# sha2017_rev0_1_0_dev.net
KiCad netlist of a schematic drawn in EAGLE
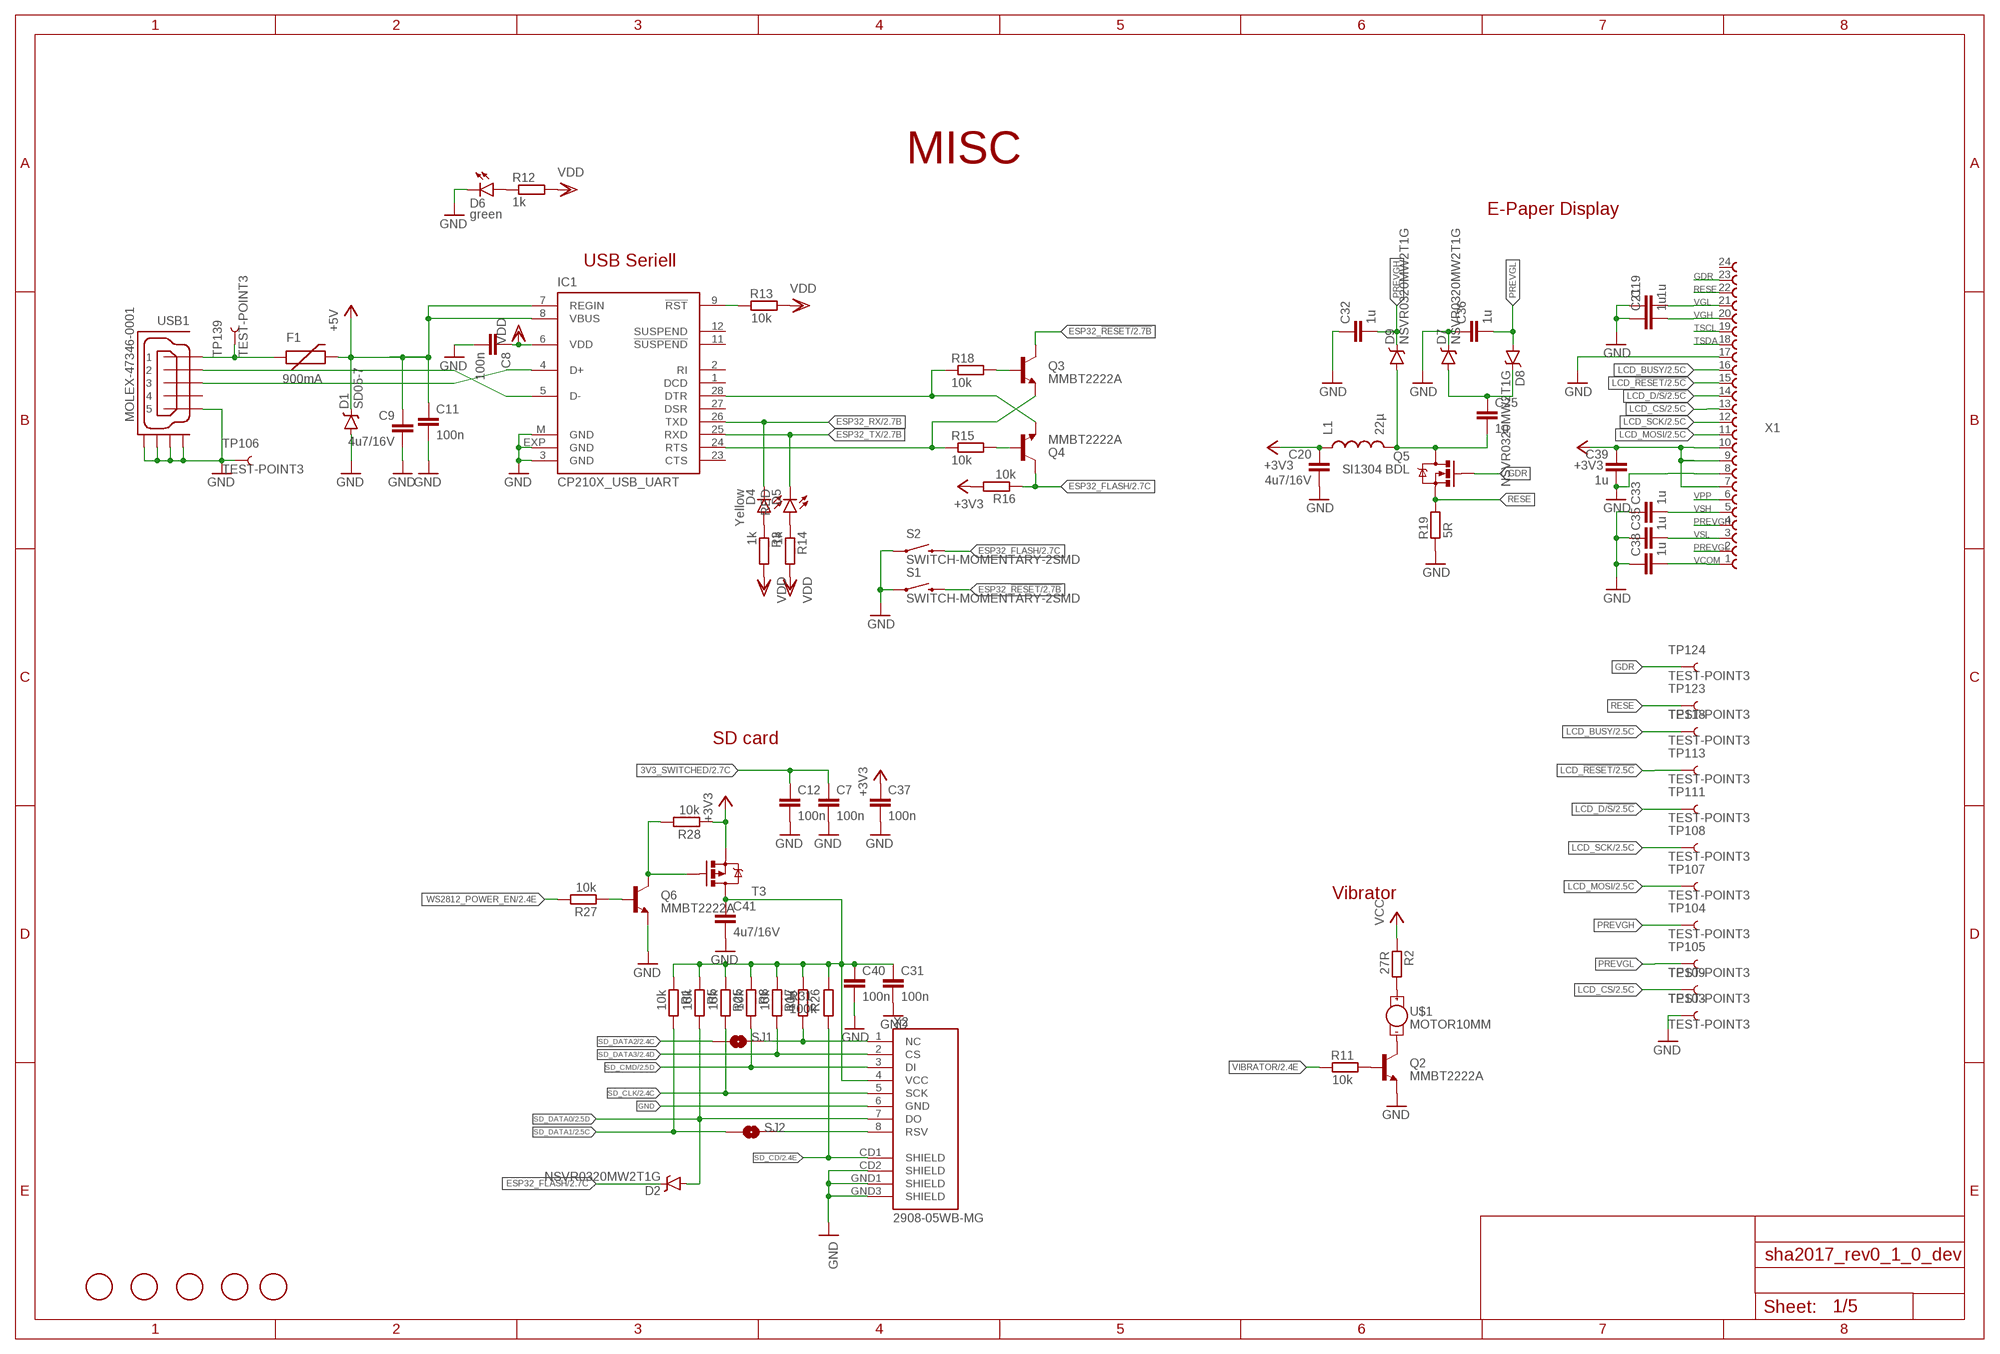
[diagram p0: schematic, sheet 1]
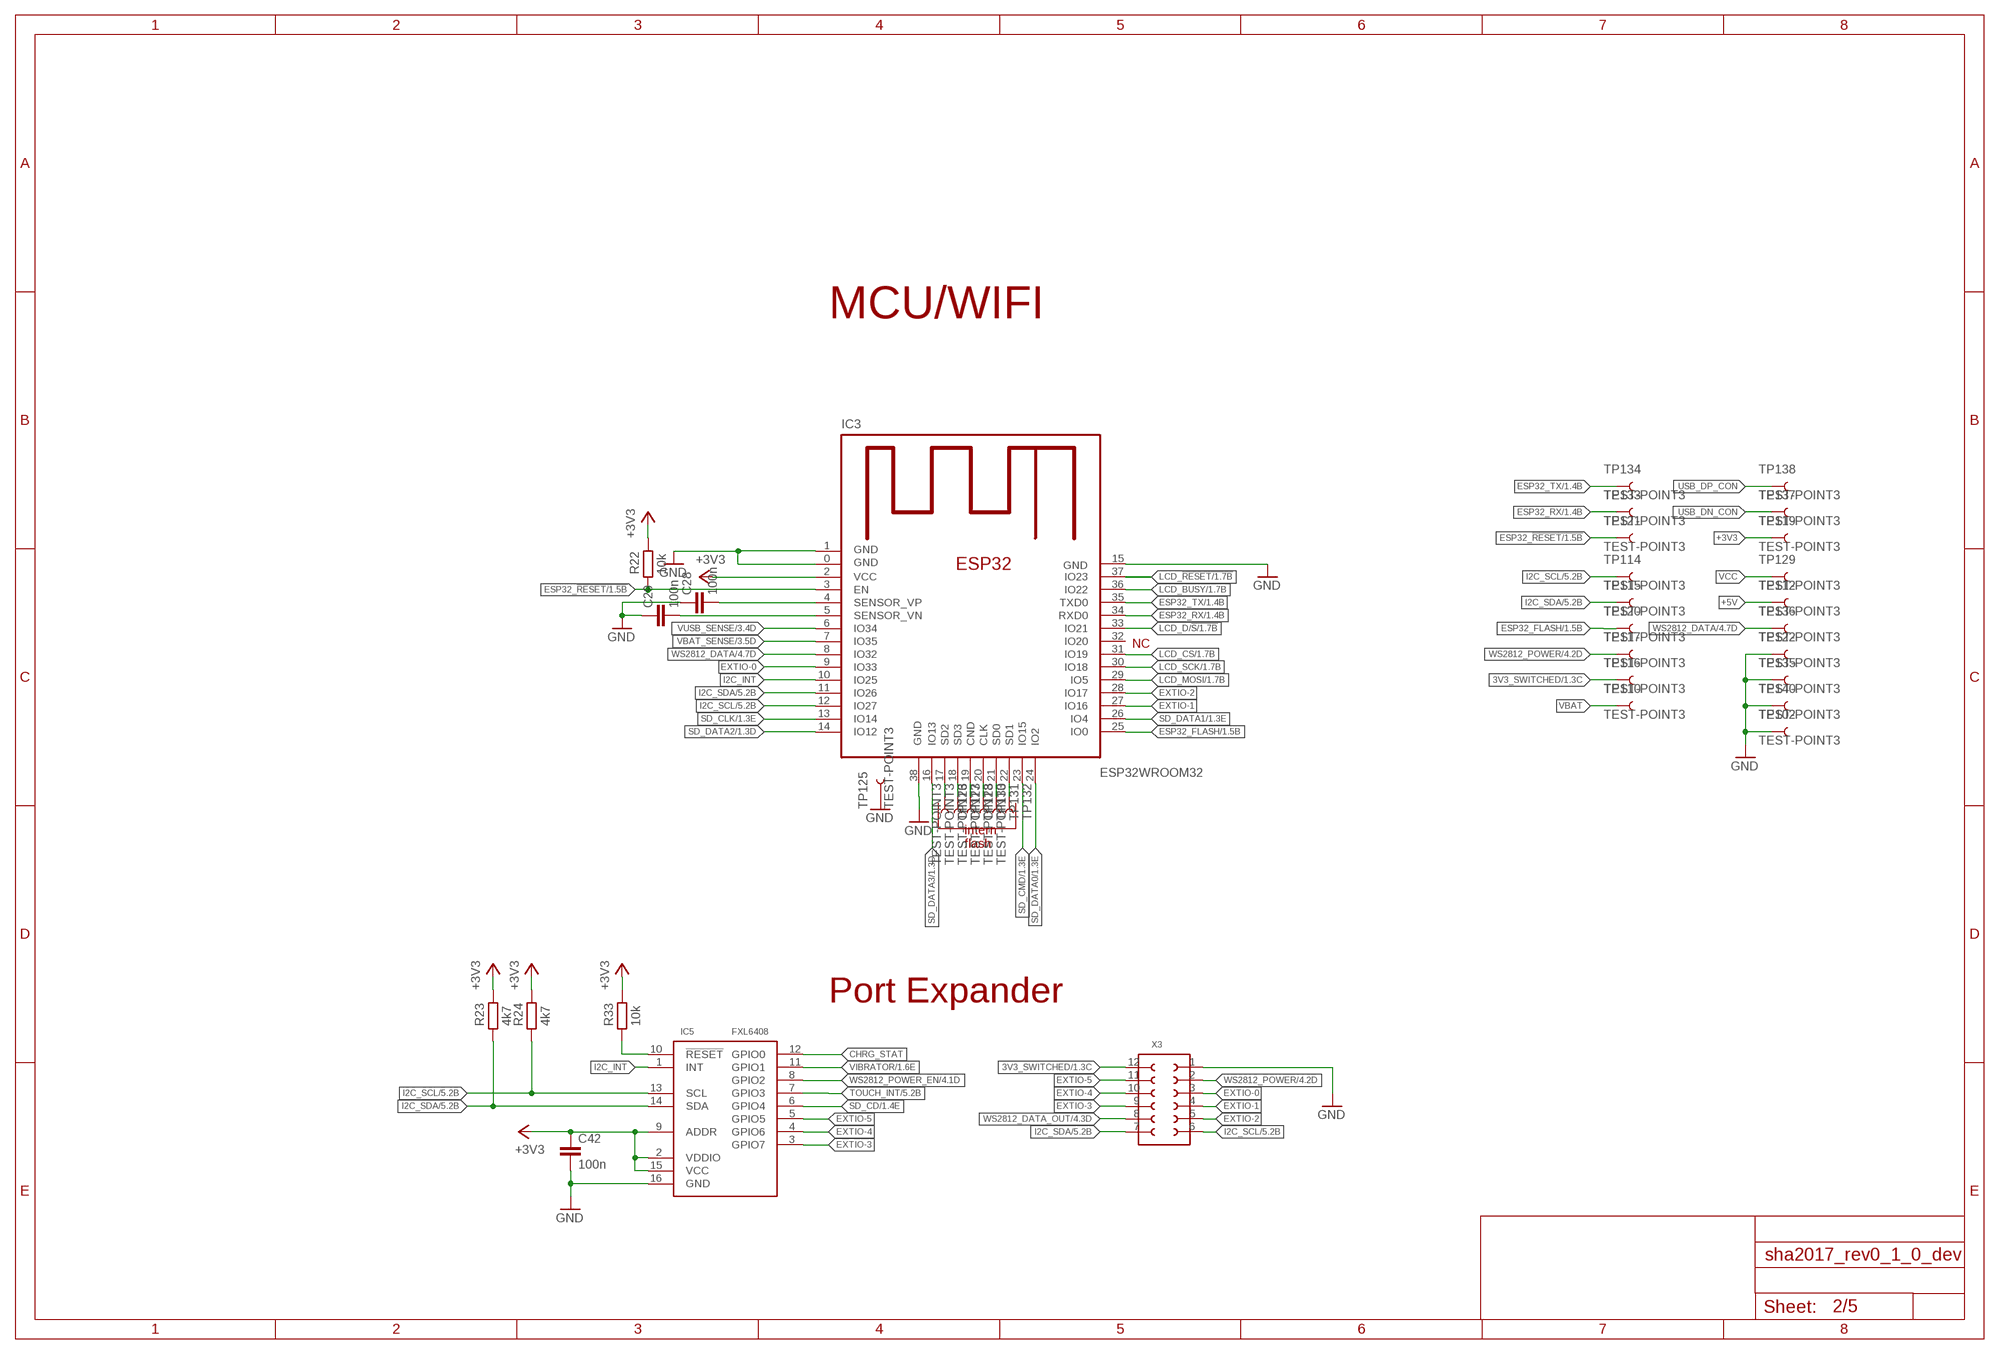
[diagram p1: schematic, sheet 2]
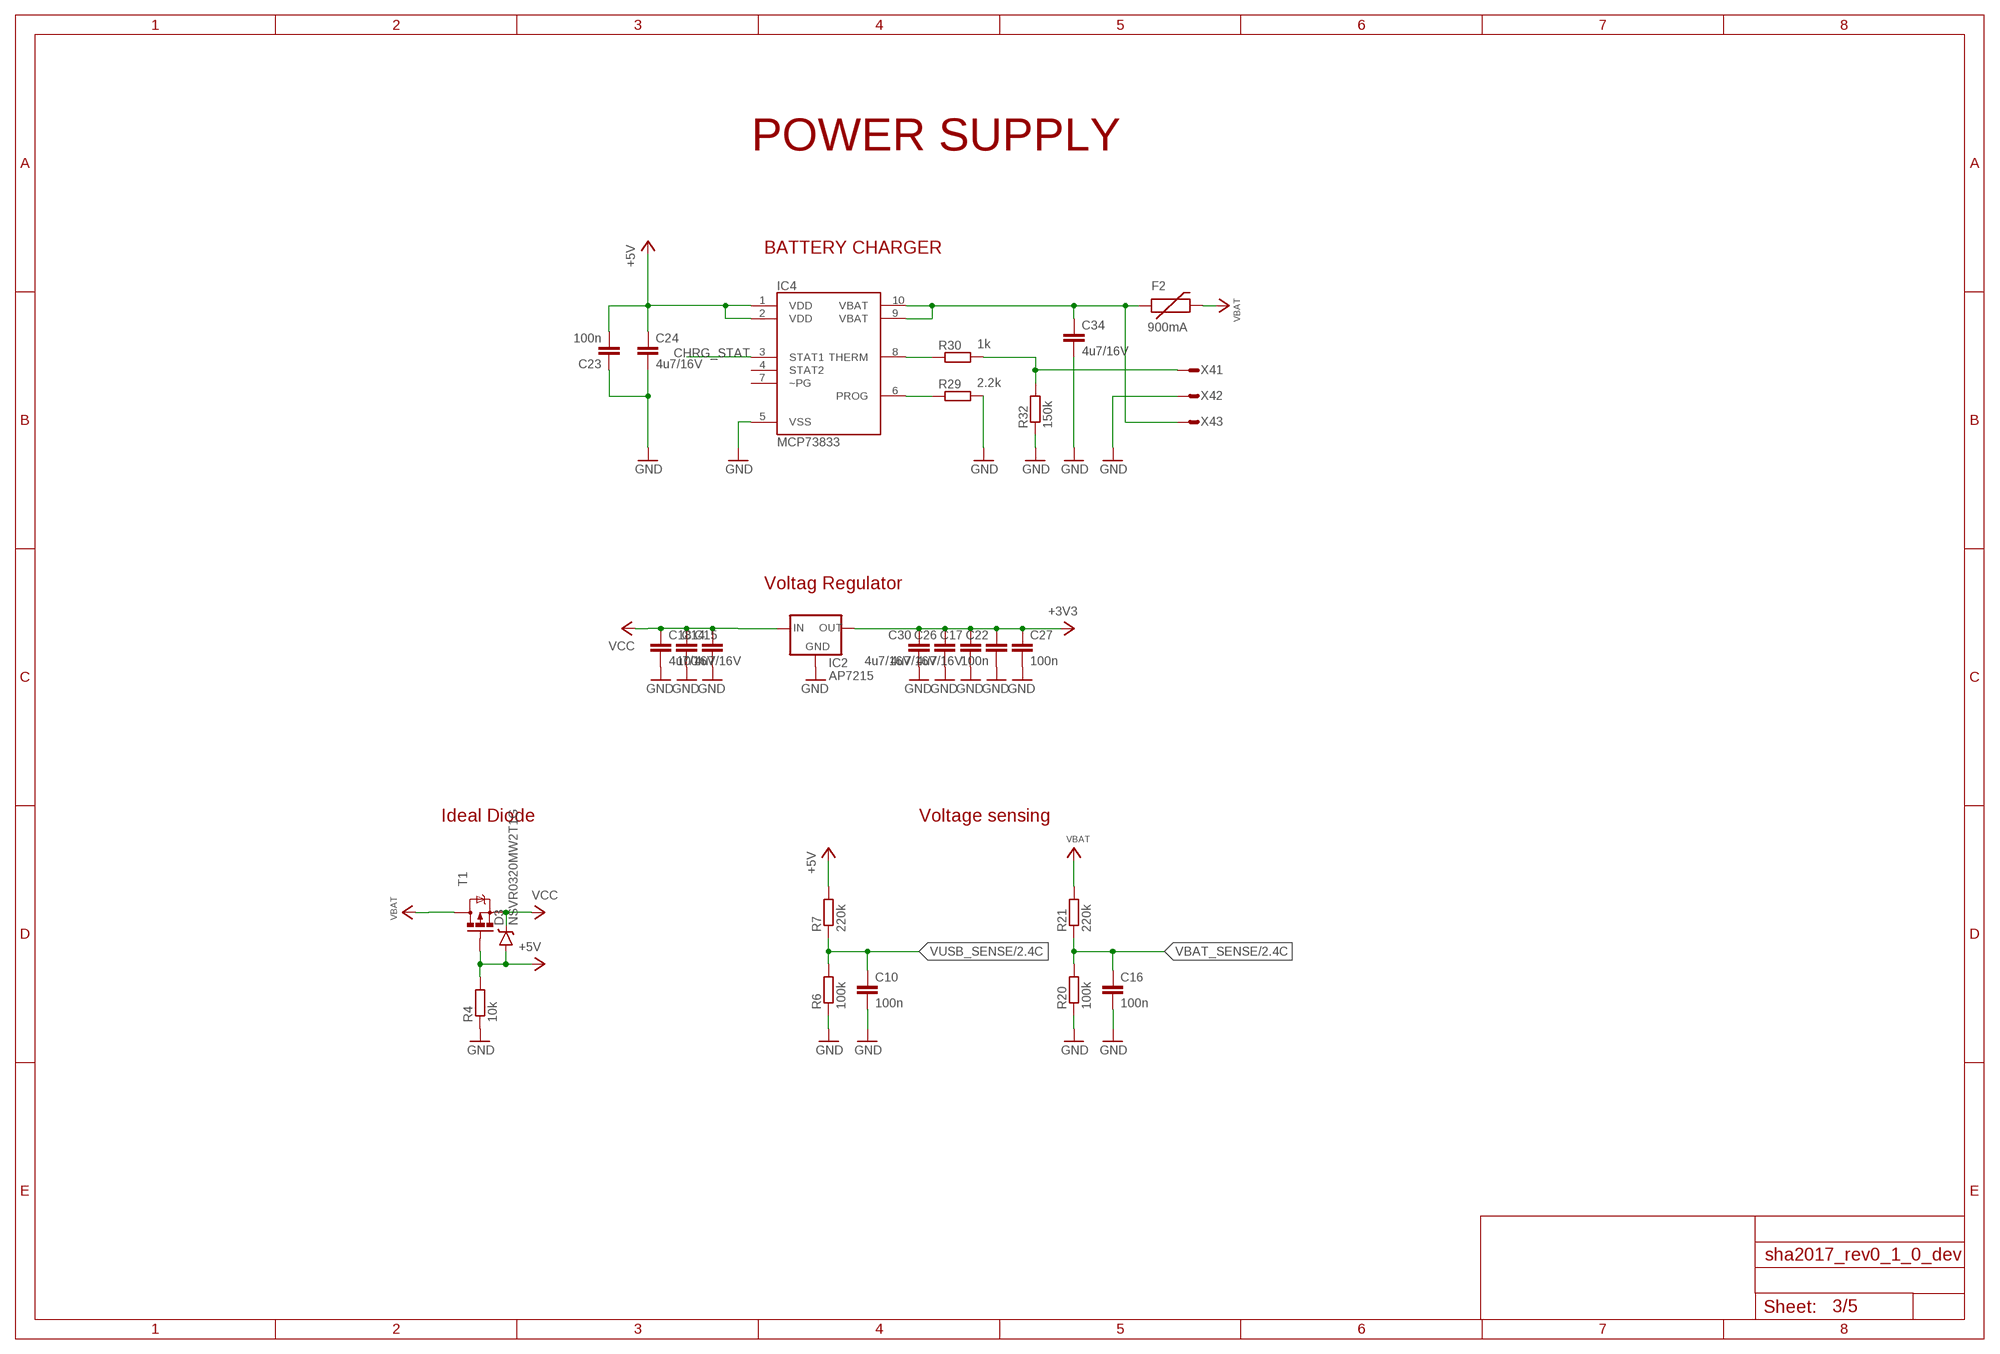
[diagram p2: schematic, sheet 3]
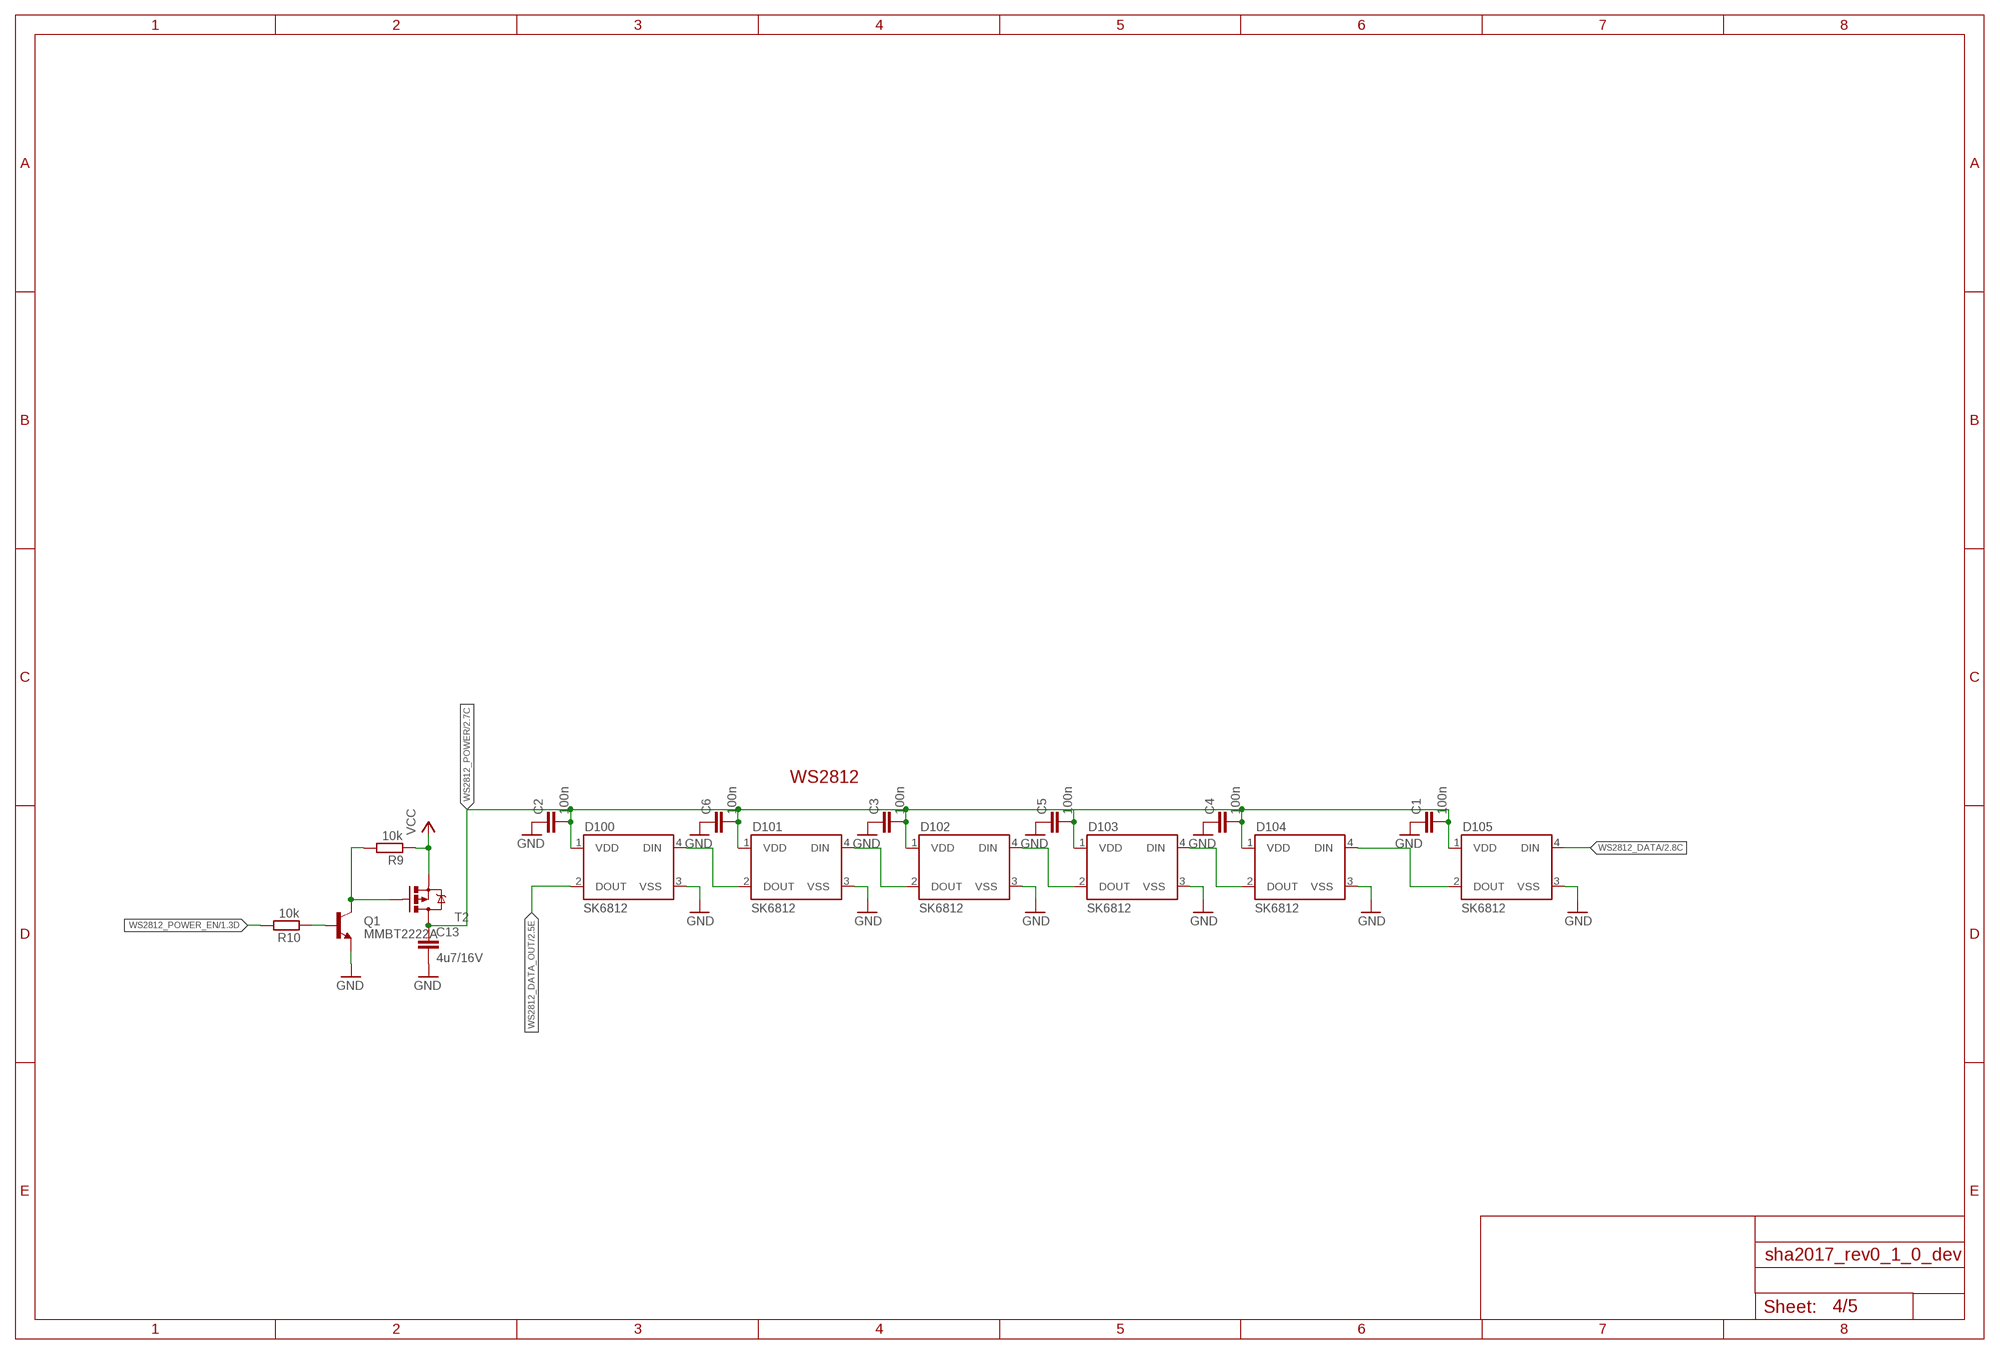
[diagram p3: schematic, sheet 4]
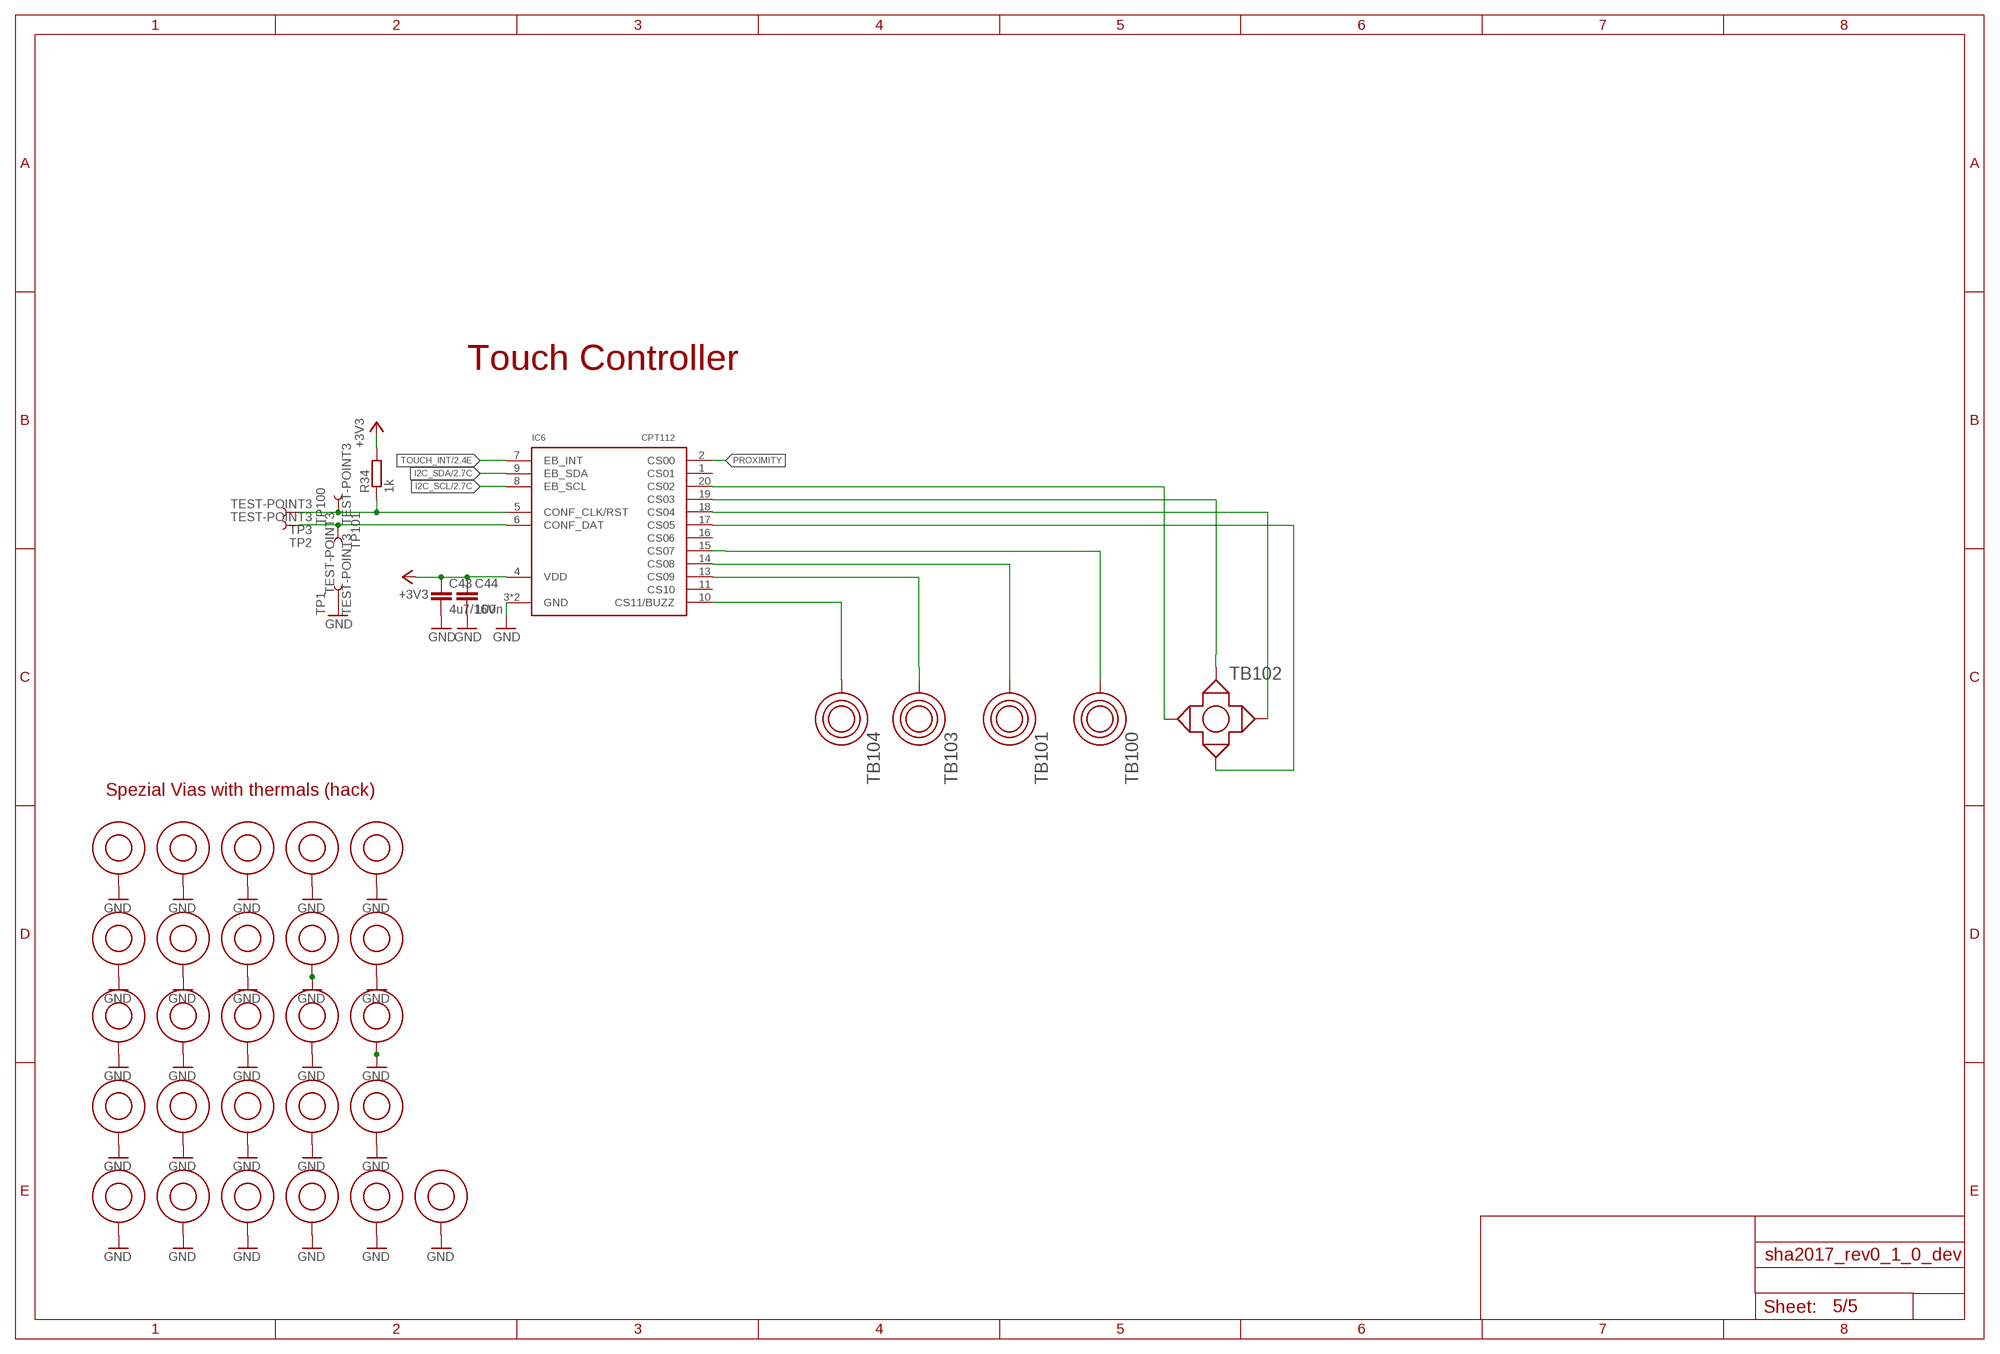
[diagram p4: schematic, sheet 5]

(export (version "E")
  (design (tool "Eeschema 10.0.6"))
  (components
    (comp (ref "C7")
      (value "100n")
      (footprint "eagle-import:C0603-DASHES")
      (fields (field (name "PARTNO") "GRM188R71H104KA93D"))
      (libsource (lib "eagle-import") (part "C0603-DASHES"))
    )
    (comp (ref "C8")
      (value "100n")
      (footprint "eagle-import:C0603-DASHES")
      (fields (field (name "PARTNO") "GRM188R71H104KA93D"))
      (libsource (lib "eagle-import") (part "C0603-DASHES"))
    )
    (comp (ref "C9")
      (value "4u7/16V")
      (footprint "eagle-import:C0805")
      (fields (field (name "PARTNO") "GRM21BR61C475KA88K"))
      (libsource (lib "eagle-import") (part "C-EUC0805"))
    )
    (comp (ref "C11")
      (value "100n")
      (footprint "eagle-import:C0603-DASHES")
      (fields (field (name "PARTNO") "GRM188R71H104KA93D"))
      (libsource (lib "eagle-import") (part "C0603-DASHES"))
    )
    (comp (ref "C12")
      (value "100n")
      (footprint "eagle-import:C0603-DASHES")
      (fields (field (name "PARTNO") "GRM188R71H104KA93D"))
      (libsource (lib "eagle-import") (part "C0603-DASHES"))
    )
    (comp (ref "C19")
      (value "1u")
      (footprint "eagle-import:C0603-DASHES")
      (fields (field (name "PARTNO") "GRM188R61E105KA12D"))
      (libsource (lib "eagle-import") (part "C0603-DASHES"))
    )
    (comp (ref "C20")
      (value "4u7/16V")
      (footprint "eagle-import:C0805")
      (fields (field (name "PARTNO") "GRM21BR61C475KA88K"))
      (libsource (lib "eagle-import") (part "C-EUC0805"))
    )
    (comp (ref "C21")
      (value "1u")
      (footprint "eagle-import:C0603-DASHES")
      (fields (field (name "PARTNO") "GRM188R61E105KA12D"))
      (libsource (lib "eagle-import") (part "C0603-DASHES"))
    )
    (comp (ref "C25")
      (value "1u")
      (footprint "eagle-import:C0603-DASHES")
      (fields (field (name "PARTNO") "GRM188R61E105KA12D"))
      (libsource (lib "eagle-import") (part "C0603-DASHES"))
    )
    (comp (ref "C31")
      (value "100n")
      (footprint "eagle-import:C0603-DASHES")
      (fields (field (name "PARTNO") "GRM188R71H104KA93D"))
      (libsource (lib "eagle-import") (part "C0603-DASHES"))
    )
    (comp (ref "C32")
      (value "1u")
      (footprint "eagle-import:C0603-DASHES")
      (fields (field (name "PARTNO") "GRM188R61E105KA12D"))
      (libsource (lib "eagle-import") (part "C0603-DASHES"))
    )
    (comp (ref "C33")
      (value "1u")
      (footprint "eagle-import:C0603-DASHES")
      (fields (field (name "PARTNO") "GRM188R61E105KA12D"))
      (libsource (lib "eagle-import") (part "C0603-DASHES"))
    )
    (comp (ref "C35")
      (value "1u")
      (footprint "eagle-import:C0603-DASHES")
      (fields (field (name "PARTNO") "GRM188R61E105KA12D"))
      (libsource (lib "eagle-import") (part "C0603-DASHES"))
    )
    (comp (ref "C36")
      (value "1u")
      (footprint "eagle-import:C0603-DASHES")
      (fields (field (name "PARTNO") "GRM188R61E105KA12D"))
      (libsource (lib "eagle-import") (part "C0603-DASHES"))
    )
    (comp (ref "C37")
      (value "100n")
      (footprint "eagle-import:C0603-DASHES")
      (fields (field (name "PARTNO") "GRM188R71H104KA93D"))
      (libsource (lib "eagle-import") (part "C0603-DASHES"))
    )
    (comp (ref "C38")
      (value "1u")
      (footprint "eagle-import:C0603-DASHES")
      (fields (field (name "PARTNO") "GRM188R61E105KA12D"))
      (libsource (lib "eagle-import") (part "C0603-DASHES"))
    )
    (comp (ref "C39")
      (value "1u")
      (footprint "eagle-import:C0603-DASHES")
      (fields (field (name "PARTNO") "GRM188R61E105KA12D"))
      (libsource (lib "eagle-import") (part "C0603-DASHES"))
    )
    (comp (ref "C40")
      (value "100n")
      (footprint "eagle-import:C0603-DASHES")
      (fields (field (name "PARTNO") "GRM188R71H104KA93D"))
      (libsource (lib "eagle-import") (part "C0603-DASHES"))
    )
    (comp (ref "C41")
      (value "4u7/16V")
      (footprint "eagle-import:C0805")
      (fields (field (name "PARTNO") "GRM21BR61C475KA88K"))
      (libsource (lib "eagle-import") (part "C-EUC0805"))
    )
    (comp (ref "D1")
      (value "SD05-7")
      (footprint "eagle-import:SOD-323")
      (libsource (lib "eagle-import") (part "DIODE-SCHOTTKY-PMEG4005EJ"))
    )
    (comp (ref "D2")
      (value "NSVR0320MW2T1G")
      (footprint "eagle-import:SOD-323")
      (fields (field (name "PARTNO") "BAT20JFILM"))
      (libsource (lib "eagle-import") (part "BAT20JFILM"))
    )
    (comp (ref "D4")
      (value "Yellow")
      (footprint "eagle-import:LED-0603")
      (libsource (lib "eagle-import") (part "LED0603"))
    )
    (comp (ref "D5")
      (value "RED")
      (footprint "eagle-import:LED-0603")
      (libsource (lib "eagle-import") (part "LED0603"))
    )
    (comp (ref "D6")
      (value "green")
      (footprint "eagle-import:LED-0603")
      (libsource (lib "eagle-import") (part "LED0603"))
    )
    (comp (ref "D7")
      (value "NSVR0320MW2T1G")
      (footprint "eagle-import:SOD-323")
      (fields (field (name "PARTNO") "BAT20JFILM"))
      (libsource (lib "eagle-import") (part "BAT20JFILM"))
    )
    (comp (ref "D8")
      (value "NSVR0320MW2T1G")
      (footprint "eagle-import:SOD-323")
      (fields (field (name "PARTNO") "BAT20JFILM"))
      (libsource (lib "eagle-import") (part "BAT20JFILM"))
    )
    (comp (ref "D9")
      (value "NSVR0320MW2T1G")
      (footprint "eagle-import:SOD-323")
      (fields (field (name "PARTNO") "BAT20JFILM"))
      (libsource (lib "eagle-import") (part "BAT20JFILM"))
    )
    (comp (ref "F1")
      (value "900mA")
      (footprint "eagle-import:PTC-1206")
      (libsource (lib "eagle-import") (part "PTCSMD"))
    )
    (comp (ref "FD1")
      (value "FIDUCIAL")
      (footprint "eagle-import:FIDUCIAL_1MM")
      (fields (field (name "PARTNO") "NAP"))
      (libsource (lib "eagle-import") (part "FIDUCIAL"))
    )
    (comp (ref "FD2")
      (value "FIDUCIAL")
      (footprint "eagle-import:FIDUCIAL_1MM")
      (fields (field (name "PARTNO") "NAP"))
      (libsource (lib "eagle-import") (part "FIDUCIAL"))
    )
    (comp (ref "FD3")
      (value "FIDUCIAL")
      (footprint "eagle-import:FIDUCIAL_1MM")
      (fields (field (name "PARTNO") "NAP"))
      (libsource (lib "eagle-import") (part "FIDUCIAL"))
    )
    (comp (ref "FD4")
      (value "FIDUCIAL")
      (footprint "eagle-import:FIDUCIAL_1MM")
      (fields (field (name "PARTNO") "NAP"))
      (libsource (lib "eagle-import") (part "FIDUCIAL"))
    )
    (comp (ref "FD5")
      (value "FIDUCIAL")
      (footprint "eagle-import:FIDUCIAL_1MM")
      (fields (field (name "PARTNO") "NAP"))
      (libsource (lib "eagle-import") (part "FIDUCIAL"))
    )
    (comp (ref "IC1")
      (value "CP210X_USB_UART")
      (footprint "eagle-import:MLP28")
      (fields (field (name "PARTNO") "CP2102-GMR"))
      (libsource (lib "eagle-import") (part "CP210X_USB_UART"))
    )
    (comp (ref "L1")
      (value "22µ")
      (footprint "eagle-import:1210")
      (fields (field (name "PARTNO") "NLCV32T-220K-EF"))
      (libsource (lib "eagle-import") (part "INDUCTOR1210"))
    )
    (comp (ref "Q2")
      (value "MMBT2222A")
      (footprint "eagle-import:SOT23-3")
      (fields (field (name "PARTNO") "BC817-25,215"))
      (libsource (lib "eagle-import") (part "TRANSISTOR_NPNMMBT2222A"))
    )
    (comp (ref "Q3")
      (value "MMBT2222A")
      (footprint "eagle-import:SOT23-3")
      (fields (field (name "PARTNO") "BC817-25,215"))
      (libsource (lib "eagle-import") (part "TRANSISTOR_NPNMMBT2222A"))
    )
    (comp (ref "Q4")
      (value "MMBT2222A")
      (footprint "eagle-import:SOT23-3")
      (fields (field (name "PARTNO") "BC817-25,215"))
      (libsource (lib "eagle-import") (part "TRANSISTOR_NPNMMBT2222A"))
    )
    (comp (ref "Q5")
      (value "SI1304 BDL")
      (footprint "eagle-import:SOT323")
      (fields (field (name "PARTNO") "SI1308EDL-T1-GE3"))
      (libsource (lib "eagle-import") (part "MOSFET-NCHANNEL2N7002PW"))
    )
    (comp (ref "Q6")
      (value "MMBT2222A")
      (footprint "eagle-import:SOT23-3")
      (fields (field (name "PARTNO") "BC817-25,215"))
      (libsource (lib "eagle-import") (part "TRANSISTOR_NPNMMBT2222A"))
    )
    (comp (ref "R1")
      (value "10k")
      (footprint "eagle-import:R0603-DASHES")
      (fields (field (name "PARTNO") "ERJ-3GEYJ103V"))
      (libsource (lib "eagle-import") (part "R0603-DASHES"))
    )
    (comp (ref "R2")
      (value "27R")
      (footprint "eagle-import:R0603-DASHES")
      (fields (field (name "PARTNO") "ERJ-3GEYJ220V"))
      (libsource (lib "eagle-import") (part "R0603-DASHES"))
    )
    (comp (ref "R3")
      (value "1k")
      (footprint "eagle-import:R0603-DASHES")
      (fields (field (name "PARTNO") "ERJ-3GEYJ102V"))
      (libsource (lib "eagle-import") (part "sha2017_rev0_1_0_dev_R0603-DASHES"))
    )
    (comp (ref "R5")
      (value "10k")
      (footprint "eagle-import:R0603-DASHES")
      (fields (field (name "PARTNO") "ERJ-3GEYJ103V"))
      (libsource (lib "eagle-import") (part "R0603-DASHES"))
    )
    (comp (ref "R8")
      (value "10k")
      (footprint "eagle-import:R0603-DASHES")
      (fields (field (name "PARTNO") "ERJ-3GEYJ103V"))
      (libsource (lib "eagle-import") (part "R0603-DASHES"))
    )
    (comp (ref "R11")
      (value "10k")
      (footprint "eagle-import:R0603-DASHES")
      (fields (field (name "PARTNO") "ERJ-3GEYJ103V"))
      (libsource (lib "eagle-import") (part "R0603-DASHES"))
    )
    (comp (ref "R12")
      (value "1k")
      (footprint "eagle-import:R0603-DASHES")
      (fields (field (name "PARTNO") "ERJ-3GEYJ102V"))
      (libsource (lib "eagle-import") (part "sha2017_rev0_1_0_dev_R0603-DASHES"))
    )
    (comp (ref "R13")
      (value "10k")
      (footprint "eagle-import:R0603-DASHES")
      (fields (field (name "PARTNO") "ERJ-3GEYJ103V"))
      (libsource (lib "eagle-import") (part "sha2017_rev0_1_0_dev_R0603-DASHES"))
    )
    (comp (ref "R14")
      (value "1k")
      (footprint "eagle-import:R0603-DASHES")
      (fields (field (name "PARTNO") "ERJ-3GEYJ102V"))
      (libsource (lib "eagle-import") (part "sha2017_rev0_1_0_dev_R0603-DASHES"))
    )
    (comp (ref "R15")
      (value "10k")
      (footprint "eagle-import:R0603-DASHES")
      (fields (field (name "PARTNO") "ERJ-3GEYJ103V"))
      (libsource (lib "eagle-import") (part "sha2017_rev0_1_0_dev_R0603-DASHES"))
    )
    (comp (ref "R16")
      (value "10k")
      (footprint "eagle-import:R0603-DASHES")
      (fields (field (name "PARTNO") "ERJ-3GEYJ103V"))
      (libsource (lib "eagle-import") (part "sha2017_rev0_1_0_dev_R0603-DASHES"))
    )
    (comp (ref "R17")
      (value "10k")
      (footprint "eagle-import:R0603-DASHES")
      (fields (field (name "PARTNO") "ERJ-3GEYJ103V"))
      (libsource (lib "eagle-import") (part "sha2017_rev0_1_0_dev_R0603-DASHES"))
    )
    (comp (ref "R18")
      (value "10k")
      (footprint "eagle-import:R0603-DASHES")
      (fields (field (name "PARTNO") "ERJ-3GEYJ103V"))
      (libsource (lib "eagle-import") (part "sha2017_rev0_1_0_dev_R0603-DASHES"))
    )
    (comp (ref "R19")
      (value "5R")
      (footprint "eagle-import:R0603-DASHES")
      (fields (field (name "PARTNO") "ERJ-3GEYJ5R1V"))
      (libsource (lib "eagle-import") (part "sha2017_rev0_1_0_dev_R0603-DASHES"))
    )
    (comp (ref "R25")
      (value "10k")
      (footprint "eagle-import:R0603-DASHES")
      (fields (field (name "PARTNO") "ERJ-3GEYJ103V"))
      (libsource (lib "eagle-import") (part "sha2017_rev0_1_0_dev_R0603-DASHES"))
    )
    (comp (ref "R26")
      (value "10k")
      (footprint "eagle-import:R0603-DASHES")
      (fields (field (name "PARTNO") "ERJ-3GEYJ103V"))
      (libsource (lib "eagle-import") (part "sha2017_rev0_1_0_dev_R0603-DASHES"))
    )
    (comp (ref "R27")
      (value "10k")
      (footprint "eagle-import:R0603-DASHES")
      (fields (field (name "PARTNO") "ERJ-3GEYJ103V"))
      (libsource (lib "eagle-import") (part "R0603-DASHES"))
    )
    (comp (ref "R28")
      (value "10k")
      (footprint "eagle-import:R0603-DASHES")
      (fields (field (name "PARTNO") "ERJ-3GEYJ103V"))
      (libsource (lib "eagle-import") (part "R0603-DASHES"))
    )
    (comp (ref "R31")
      (value "100k")
      (footprint "eagle-import:R0603-DASHES")
      (fields (field (name "PARTNO") "ERJ-3GEYJ104V"))
      (libsource (lib "eagle-import") (part "sha2017_rev0_1_0_dev_R0603-DASHES"))
    )
    (comp (ref "S1")
      (value "SWITCH-MOMENTARY-2SMD")
      (footprint "eagle-import:TACTILE-SWITCH-SMD")
      (fields (field (name "PARTNO") "SKQGABE010"))
      (libsource (lib "eagle-import") (part "SWITCH-MOMENTARY-2SMD"))
    )
    (comp (ref "S2")
      (value "SWITCH-MOMENTARY-2SMD")
      (footprint "eagle-import:TACTILE-SWITCH-SMD")
      (fields (field (name "PARTNO") "SKQGABE010"))
      (libsource (lib "eagle-import") (part "SWITCH-MOMENTARY-2SMD"))
    )
    (comp (ref "SJ1")
      (value "JUMPER-PAD-2-NOYES_SILK")
      (footprint "eagle-import:PAD-JUMPER-2-NO_YES_SILK")
      (fields (field (name "PARTNO") "NAP"))
      (libsource (lib "eagle-import") (part "JUMPER-PAD-2-NOYES_SILK"))
    )
    (comp (ref "SJ2")
      (value "JUMPER-PAD-2-NOYES_SILK")
      (footprint "eagle-import:PAD-JUMPER-2-NO_YES_SILK")
      (fields (field (name "PARTNO") "NAP"))
      (libsource (lib "eagle-import") (part "JUMPER-PAD-2-NOYES_SILK"))
    )
    (comp (ref "T3")
      (value "MOSFET-PCHANNEL")
      (footprint "eagle-import:SOT23-3")
      (libsource (lib "eagle-import") (part "MOSFET-PCHANNEL"))
    )
    (comp (ref "TP103")
      (value "TEST-POINT3")
      (footprint "eagle-import:PAD.03X.03")
      (fields (field (name "PARTNO") "NAP"))
      (libsource (lib "eagle-import") (part "TEST-POINT3"))
    )
    (comp (ref "TP104")
      (value "TEST-POINT3")
      (footprint "eagle-import:PAD.03X.03")
      (fields (field (name "PARTNO") "NAP"))
      (libsource (lib "eagle-import") (part "TEST-POINT3"))
    )
    (comp (ref "TP105")
      (value "TEST-POINT3")
      (footprint "eagle-import:PAD.03X.03")
      (fields (field (name "PARTNO") "NAP"))
      (libsource (lib "eagle-import") (part "TEST-POINT3"))
    )
    (comp (ref "TP106")
      (value "TEST-POINT3")
      (footprint "eagle-import:PAD.03X.03")
      (fields (field (name "PARTNO") "NAP"))
      (libsource (lib "eagle-import") (part "TEST-POINT3"))
    )
    (comp (ref "TP107")
      (value "TEST-POINT3")
      (footprint "eagle-import:PAD.03X.03")
      (fields (field (name "PARTNO") "NAP"))
      (libsource (lib "eagle-import") (part "TEST-POINT3"))
    )
    (comp (ref "TP108")
      (value "TEST-POINT3")
      (footprint "eagle-import:PAD.03X.03")
      (fields (field (name "PARTNO") "NAP"))
      (libsource (lib "eagle-import") (part "TEST-POINT3"))
    )
    (comp (ref "TP109")
      (value "TEST-POINT3")
      (footprint "eagle-import:PAD.03X.03")
      (fields (field (name "PARTNO") "NAP"))
      (libsource (lib "eagle-import") (part "TEST-POINT3"))
    )
    (comp (ref "TP111")
      (value "TEST-POINT3")
      (footprint "eagle-import:PAD.03X.03")
      (fields (field (name "PARTNO") "NAP"))
      (libsource (lib "eagle-import") (part "TEST-POINT3"))
    )
    (comp (ref "TP113")
      (value "TEST-POINT3")
      (footprint "eagle-import:PAD.03X.03")
      (fields (field (name "PARTNO") "NAP"))
      (libsource (lib "eagle-import") (part "TEST-POINT3"))
    )
    (comp (ref "TP118")
      (value "TEST-POINT3")
      (footprint "eagle-import:PAD.03X.03")
      (fields (field (name "PARTNO") "NAP"))
      (libsource (lib "eagle-import") (part "TEST-POINT3"))
    )
    (comp (ref "TP123")
      (value "TEST-POINT3")
      (footprint "eagle-import:PAD.03X.03")
      (fields (field (name "PARTNO") "NAP"))
      (libsource (lib "eagle-import") (part "TEST-POINT3"))
    )
    (comp (ref "TP124")
      (value "TEST-POINT3")
      (footprint "eagle-import:PAD.03X.03")
      (fields (field (name "PARTNO") "NAP"))
      (libsource (lib "eagle-import") (part "TEST-POINT3"))
    )
    (comp (ref "TP139")
      (value "TEST-POINT3")
      (footprint "eagle-import:PAD.03X.03")
      (fields (field (name "PARTNO") "NAP"))
      (libsource (lib "eagle-import") (part "TEST-POINT3"))
    )
    (comp (ref "U$1")
      (value "MOTOR10MM")
      (footprint "eagle-import:VIBE-MOTOR-10MM")
      (libsource (lib "eagle-import") (part "MOTOR10MM"))
    )
    (comp (ref "USB1")
      (value "MOLEX-47346-0001")
      (footprint "eagle-import:MOLEX-47364-0001")
      (fields (field (name "PARTNO") "10118192-0001LF"))
      (libsource (lib "eagle-import") (part "MOLEX-47346-0001"))
    )
    (comp (ref "X1")
      (value "68712414022")
      (footprint "eagle-import:68712414022")
      (libsource (lib "eagle-import") (part "68712414022"))
    )
    (comp (ref "X2")
      (value "2908-05WB-MG")
      (footprint "eagle-import:MICRO-SD-SOCKET-PP")
      (libsource (lib "eagle-import") (part "2908-05WB-MG"))
    )
    (comp (ref "C28")
      (value "100n")
      (footprint "eagle-import:C0603-DASHES")
      (fields (field (name "PARTNO") "GRM188R71H104KA93D"))
      (libsource (lib "eagle-import") (part "C0603-DASHES"))
    )
    (comp (ref "C29")
      (value "100n")
      (footprint "eagle-import:C0603-DASHES")
      (fields (field (name "PARTNO") "GRM188R71H104KA93D"))
      (libsource (lib "eagle-import") (part "C0603-DASHES"))
    )
    (comp (ref "C42")
      (value "100n")
      (footprint "eagle-import:C0603-DASHES")
      (fields (field (name "PARTNO") "GRM188R71H104KA93D"))
      (libsource (lib "eagle-import") (part "C0603-DASHES"))
    )
    (comp (ref "IC3")
      (value "ESP32WROOM32")
      (footprint "eagle-import:ESP32MOD")
      (libsource (lib "eagle-import") (part "ESP32WROOM32"))
    )
    (comp (ref "IC5")
      (value "FXL6408")
      (footprint "eagle-import:UMLP-16")
      (fields (field (name "PARTNO") "FXL6408UMX"))
      (libsource (lib "eagle-import") (part "FXL6408"))
    )
    (comp (ref "R22")
      (value "10k")
      (footprint "eagle-import:R0603-DASHES")
      (fields (field (name "PARTNO") "ERJ-3GEYJ103V"))
      (libsource (lib "eagle-import") (part "sha2017_rev0_1_0_dev_R0603-DASHES"))
    )
    (comp (ref "R23")
      (value "4k7")
      (footprint "eagle-import:R0603-DASHES")
      (fields (field (name "PARTNO") "ERJ-3GEYJ103V"))
      (libsource (lib "eagle-import") (part "sha2017_rev0_1_0_dev_R0603-DASHES"))
    )
    (comp (ref "R24")
      (value "4k7")
      (footprint "eagle-import:R0603-DASHES")
      (fields (field (name "PARTNO") "ERJ-3GEYJ103V"))
      (libsource (lib "eagle-import") (part "sha2017_rev0_1_0_dev_R0603-DASHES"))
    )
    (comp (ref "R33")
      (value "10k")
      (footprint "eagle-import:R0603-DASHES")
      (fields (field (name "PARTNO") "ERJ-3GEYJ103V"))
      (libsource (lib "eagle-import") (part "sha2017_rev0_1_0_dev_R0603-DASHES"))
    )
    (comp (ref "TP102")
      (value "TEST-POINT3")
      (footprint "eagle-import:PAD.03X.03")
      (fields (field (name "PARTNO") "NAP"))
      (libsource (lib "eagle-import") (part "TEST-POINT3"))
    )
    (comp (ref "TP110")
      (value "TEST-POINT3")
      (footprint "eagle-import:PAD.03X.03")
      (fields (field (name "PARTNO") "NAP"))
      (libsource (lib "eagle-import") (part "TEST-POINT3"))
    )
    (comp (ref "TP112")
      (value "TEST-POINT3")
      (footprint "eagle-import:PAD.03X.03")
      (fields (field (name "PARTNO") "NAP"))
      (libsource (lib "eagle-import") (part "TEST-POINT3"))
    )
    (comp (ref "TP114")
      (value "TEST-POINT3")
      (footprint "eagle-import:PAD.03X.03")
      (fields (field (name "PARTNO") "NAP"))
      (libsource (lib "eagle-import") (part "TEST-POINT3"))
    )
    (comp (ref "TP115")
      (value "TEST-POINT3")
      (footprint "eagle-import:PAD.03X.03")
      (fields (field (name "PARTNO") "NAP"))
      (libsource (lib "eagle-import") (part "TEST-POINT3"))
    )
    (comp (ref "TP116")
      (value "TEST-POINT3")
      (footprint "eagle-import:PAD.03X.03")
      (fields (field (name "PARTNO") "NAP"))
      (libsource (lib "eagle-import") (part "TEST-POINT3"))
    )
    (comp (ref "TP117")
      (value "TEST-POINT3")
      (footprint "eagle-import:PAD.03X.03")
      (fields (field (name "PARTNO") "NAP"))
      (libsource (lib "eagle-import") (part "TEST-POINT3"))
    )
    (comp (ref "TP119")
      (value "TEST-POINT3")
      (footprint "eagle-import:PAD.03X.03")
      (fields (field (name "PARTNO") "NAP"))
      (libsource (lib "eagle-import") (part "TEST-POINT3"))
    )
    (comp (ref "TP120")
      (value "TEST-POINT3")
      (footprint "eagle-import:PAD.03X.03")
      (fields (field (name "PARTNO") "NAP"))
      (libsource (lib "eagle-import") (part "TEST-POINT3"))
    )
    (comp (ref "TP121")
      (value "TEST-POINT3")
      (footprint "eagle-import:PAD.03X.03")
      (fields (field (name "PARTNO") "NAP"))
      (libsource (lib "eagle-import") (part "TEST-POINT3"))
    )
    (comp (ref "TP122")
      (value "TEST-POINT3")
      (footprint "eagle-import:PAD.03X.03")
      (fields (field (name "PARTNO") "NAP"))
      (libsource (lib "eagle-import") (part "TEST-POINT3"))
    )
    (comp (ref "TP125")
      (value "TEST-POINT3")
      (footprint "eagle-import:PAD.03X.03")
      (fields (field (name "PARTNO") "NAP"))
      (libsource (lib "eagle-import") (part "TEST-POINT3"))
    )
    (comp (ref "TP126")
      (value "TEST-POINT3")
      (footprint "eagle-import:PAD.03X.03")
      (fields (field (name "PARTNO") "NAP"))
      (libsource (lib "eagle-import") (part "TEST-POINT3"))
    )
    (comp (ref "TP127")
      (value "TEST-POINT3")
      (footprint "eagle-import:PAD.03X.03")
      (fields (field (name "PARTNO") "NAP"))
      (libsource (lib "eagle-import") (part "TEST-POINT3"))
    )
    (comp (ref "TP128")
      (value "TEST-POINT3")
      (footprint "eagle-import:PAD.03X.03")
      (fields (field (name "PARTNO") "NAP"))
      (libsource (lib "eagle-import") (part "TEST-POINT3"))
    )
    (comp (ref "TP129")
      (value "TEST-POINT3")
      (footprint "eagle-import:PAD.03X.03")
      (fields (field (name "PARTNO") "NAP"))
      (libsource (lib "eagle-import") (part "TEST-POINT3"))
    )
    (comp (ref "TP130")
      (value "TEST-POINT3")
      (footprint "eagle-import:PAD.03X.03")
      (fields (field (name "PARTNO") "NAP"))
      (libsource (lib "eagle-import") (part "TEST-POINT3"))
    )
    (comp (ref "TP131")
      (value "TEST-POINT3")
      (footprint "eagle-import:PAD.03X.03")
      (fields (field (name "PARTNO") "NAP"))
      (libsource (lib "eagle-import") (part "TEST-POINT3"))
    )
    (comp (ref "TP132")
      (value "TEST-POINT3")
      (footprint "eagle-import:PAD.03X.03")
      (fields (field (name "PARTNO") "NAP"))
      (libsource (lib "eagle-import") (part "TEST-POINT3"))
    )
    (comp (ref "TP133")
      (value "TEST-POINT3")
      (footprint "eagle-import:PAD.03X.03")
      (fields (field (name "PARTNO") "NAP"))
      (libsource (lib "eagle-import") (part "TEST-POINT3"))
    )
    (comp (ref "TP134")
      (value "TEST-POINT3")
      (footprint "eagle-import:PAD.03X.03")
      (fields (field (name "PARTNO") "NAP"))
      (libsource (lib "eagle-import") (part "TEST-POINT3"))
    )
    (comp (ref "TP135")
      (value "TEST-POINT3")
      (footprint "eagle-import:PAD.03X.03")
      (fields (field (name "PARTNO") "NAP"))
      (libsource (lib "eagle-import") (part "TEST-POINT3"))
    )
    (comp (ref "TP136")
      (value "TEST-POINT3")
      (footprint "eagle-import:PAD.03X.03")
      (fields (field (name "PARTNO") "NAP"))
      (libsource (lib "eagle-import") (part "TEST-POINT3"))
    )
    (comp (ref "TP137")
      (value "TEST-POINT3")
      (footprint "eagle-import:PAD.03X.03")
      (fields (field (name "PARTNO") "NAP"))
      (libsource (lib "eagle-import") (part "TEST-POINT3"))
    )
    (comp (ref "TP138")
      (value "TEST-POINT3")
      (footprint "eagle-import:PAD.03X.03")
      (fields (field (name "PARTNO") "NAP"))
      (libsource (lib "eagle-import") (part "TEST-POINT3"))
    )
    (comp (ref "TP140")
      (value "TEST-POINT3")
      (footprint "eagle-import:PAD.03X.03")
      (fields (field (name "PARTNO") "NAP"))
      (libsource (lib "eagle-import") (part "TEST-POINT3"))
    )
    (comp (ref "X3")
      (value "610X12243021")
      (footprint "eagle-import:610X12243021")
      (fields (field (name "PARTNO") "517-153208-2020-TB"))
      (libsource (lib "eagle-import") (part "610X12243021"))
    )
    (comp (ref "C10")
      (value "100n")
      (footprint "eagle-import:C0603-DASHES")
      (fields (field (name "PARTNO") "GRM188R71H104KA93D"))
      (libsource (lib "eagle-import") (part "C0603-DASHES"))
    )
    (comp (ref "C14")
      (value "100n")
      (footprint "eagle-import:C0603-DASHES")
      (fields (field (name "PARTNO") "GRM188R71H104KA93D"))
      (libsource (lib "eagle-import") (part "C0603-DASHES"))
    )
    (comp (ref "C15")
      (value "4u7/16V")
      (footprint "eagle-import:C0805")
      (fields (field (name "PARTNO") "GRM21BR61C475KA88K"))
      (libsource (lib "eagle-import") (part "C-EUC0805"))
    )
    (comp (ref "C16")
      (value "100n")
      (footprint "eagle-import:C0603-DASHES")
      (fields (field (name "PARTNO") "GRM188R71H104KA93D"))
      (libsource (lib "eagle-import") (part "C0603-DASHES"))
    )
    (comp (ref "C17")
      (value "4u7/16V")
      (footprint "eagle-import:C0805")
      (fields (field (name "PARTNO") "GRM21BR61C475KA88K"))
      (libsource (lib "eagle-import") (part "C-EUC0805"))
    )
    (comp (ref "C18")
      (value "4u7/16V")
      (footprint "eagle-import:C0805")
      (fields (field (name "PARTNO") "GRM21BR61C475KA88K"))
      (libsource (lib "eagle-import") (part "C-EUC0805"))
    )
    (comp (ref "C22")
      (value "100n")
      (footprint "eagle-import:C0603-DASHES")
      (fields (field (name "PARTNO") "GRM188R71H104KA93D"))
      (libsource (lib "eagle-import") (part "C0603-DASHES"))
    )
    (comp (ref "C23")
      (value "100n")
      (footprint "eagle-import:C0603-DASHES")
      (fields (field (name "PARTNO") "GRM188R71H104KA93D"))
      (libsource (lib "eagle-import") (part "C0603-DASHES"))
    )
    (comp (ref "C24")
      (value "4u7/16V")
      (footprint "eagle-import:C0805")
      (fields (field (name "PARTNO") "GRM21BR61C475KA88K"))
      (libsource (lib "eagle-import") (part "C-EUC0805"))
    )
    (comp (ref "C26")
      (value "4u7/16V")
      (footprint "eagle-import:C0805")
      (fields (field (name "PARTNO") "GRM21BR61C475KA88K"))
      (libsource (lib "eagle-import") (part "C-EUC0805"))
    )
    (comp (ref "C27")
      (value "100n")
      (footprint "eagle-import:C0603-DASHES")
      (fields (field (name "PARTNO") "GRM188R71H104KA93D"))
      (libsource (lib "eagle-import") (part "C0603-DASHES"))
    )
    (comp (ref "C30")
      (value "4u7/16V")
      (footprint "eagle-import:C0805")
      (fields (field (name "PARTNO") "GRM21BR61C475KA88K"))
      (libsource (lib "eagle-import") (part "C-EUC0805"))
    )
    (comp (ref "C34")
      (value "4u7/16V")
      (footprint "eagle-import:C0805")
      (fields (field (name "PARTNO") "GRM21BR61C475KA88K"))
      (libsource (lib "eagle-import") (part "C-EUC0805"))
    )
    (comp (ref "D3")
      (value "NSVR0320MW2T1G")
      (footprint "eagle-import:SOD-323")
      (fields (field (name "PARTNO") "BAT20JFILM"))
      (libsource (lib "eagle-import") (part "BAT20JFILM"))
    )
    (comp (ref "F2")
      (value "900mA")
      (footprint "eagle-import:PTC-1206")
      (libsource (lib "eagle-import") (part "PTCSMD"))
    )
    (comp (ref "IC2")
      (value "AP7215")
      (footprint "eagle-import:SOT89")
      (fields (field (name "PARTNO") "AP7215-33YG-13"))
      (libsource (lib "eagle-import") (part "AP7215"))
    )
    (comp (ref "IC4")
      (value "MCP73833")
      (footprint "eagle-import:MSOP-10")
      (fields (field (name "PARTNO") "MCP73833-BZI/UN"))
      (libsource (lib "eagle-import") (part "MCP73833"))
    )
    (comp (ref "R4")
      (value "10k")
      (footprint "eagle-import:R0603-DASHES")
      (fields (field (name "PARTNO") "ERJ-3GEYJ103V"))
      (libsource (lib "eagle-import") (part "sha2017_rev0_1_0_dev_R0603-DASHES"))
    )
    (comp (ref "R6")
      (value "100k")
      (footprint "eagle-import:R0603-DASHES")
      (fields (field (name "PARTNO") "ERJ-3GEYJ104V"))
      (libsource (lib "eagle-import") (part "sha2017_rev0_1_0_dev_R0603-DASHES"))
    )
    (comp (ref "R7")
      (value "220k")
      (footprint "eagle-import:R0603-DASHES")
      (fields (field (name "PARTNO") "ERJ-3GEYJ224V"))
      (libsource (lib "eagle-import") (part "sha2017_rev0_1_0_dev_R0603-DASHES"))
    )
    (comp (ref "R20")
      (value "100k")
      (footprint "eagle-import:R0603-DASHES")
      (fields (field (name "PARTNO") "ERJ-3GEYJ104V"))
      (libsource (lib "eagle-import") (part "sha2017_rev0_1_0_dev_R0603-DASHES"))
    )
    (comp (ref "R21")
      (value "220k")
      (footprint "eagle-import:R0603-DASHES")
      (fields (field (name "PARTNO") "ERJ-3GEYJ224V"))
      (libsource (lib "eagle-import") (part "sha2017_rev0_1_0_dev_R0603-DASHES"))
    )
    (comp (ref "R29")
      (value "2.2k")
      (footprint "eagle-import:R0603-DASHES")
      (fields (field (name "PARTNO") "ERJ-3GEYJ222V"))
      (libsource (lib "eagle-import") (part "sha2017_rev0_1_0_dev_R0603-DASHES"))
    )
    (comp (ref "R30")
      (value "1k")
      (footprint "eagle-import:R0603-DASHES")
      (fields (field (name "PARTNO") "ERJ-3GEYJ102V"))
      (libsource (lib "eagle-import") (part "sha2017_rev0_1_0_dev_R0603-DASHES"))
    )
    (comp (ref "R32")
      (value "150k")
      (footprint "eagle-import:R0603-DASHES")
      (fields (field (name "PARTNO") "ERJ-3GEYJ154V"))
      (libsource (lib "eagle-import") (part "sha2017_rev0_1_0_dev_R0603-DASHES"))
    )
    (comp (ref "T1")
      (value "MOSFET-PCHANNEL")
      (footprint "eagle-import:SOT23-3")
      (libsource (lib "eagle-import") (part "MOSFET-PCHANNEL"))
    )
    (comp (ref "X4")
      (value "JST-PH3")
      (footprint "eagle-import:JST-PH3")
      (libsource (lib "eagle-import") (part "JST-PH3"))
    )
    (comp (ref "$$U$1")
      (value "VIA")
      (footprint "eagle-import:VIA")
      (fields (field (name "PARTNO") "NAP"))
      (libsource (lib "eagle-import") (part "VIA"))
    )
    (comp (ref "$$U$2")
      (value "VIA")
      (footprint "eagle-import:VIA")
      (fields (field (name "PARTNO") "NAP"))
      (libsource (lib "eagle-import") (part "VIA"))
    )
    (comp (ref "$$U$3")
      (value "VIA")
      (footprint "eagle-import:VIA")
      (fields (field (name "PARTNO") "NAP"))
      (libsource (lib "eagle-import") (part "VIA"))
    )
    (comp (ref "$$U$4")
      (value "VIA")
      (footprint "eagle-import:VIA")
      (fields (field (name "PARTNO") "NAP"))
      (libsource (lib "eagle-import") (part "VIA"))
    )
    (comp (ref "$$U$5")
      (value "VIA")
      (footprint "eagle-import:VIA")
      (fields (field (name "PARTNO") "NAP"))
      (libsource (lib "eagle-import") (part "VIA"))
    )
    (comp (ref "$$U$6")
      (value "VIA")
      (footprint "eagle-import:VIA")
      (fields (field (name "PARTNO") "NAP"))
      (libsource (lib "eagle-import") (part "VIA"))
    )
    (comp (ref "$$U$7")
      (value "VIA")
      (footprint "eagle-import:VIA")
      (fields (field (name "PARTNO") "NAP"))
      (libsource (lib "eagle-import") (part "VIA"))
    )
    (comp (ref "$$U$8")
      (value "VIA")
      (footprint "eagle-import:VIA")
      (fields (field (name "PARTNO") "NAP"))
      (libsource (lib "eagle-import") (part "VIA"))
    )
    (comp (ref "$$U$9")
      (value "VIA")
      (footprint "eagle-import:VIA")
      (fields (field (name "PARTNO") "NAP"))
      (libsource (lib "eagle-import") (part "VIA"))
    )
    (comp (ref "C43")
      (value "4u7/16V")
      (footprint "eagle-import:C0805")
      (fields (field (name "PARTNO") "GRM21BR61C475KA88K"))
      (libsource (lib "eagle-import") (part "C-EUC0805"))
    )
    (comp (ref "C44")
      (value "100n")
      (footprint "eagle-import:C0603-DASHES")
      (fields (field (name "PARTNO") "GRM188R71H104KA93D"))
      (libsource (lib "eagle-import") (part "C0603-DASHES"))
    )
    (comp (ref "IC6")
      (value "CPT112")
      (footprint "eagle-import:QFN20-3X3MM")
      (fields (field (name "PARTNO") "CPT112S-A02-GM"))
      (libsource (lib "eagle-import") (part "CPT112"))
    )
    (comp (ref "R34")
      (value "1k")
      (footprint "eagle-import:R0603-DASHES")
      (fields (field (name "PARTNO") "ERJ-3GEYJ102V"))
      (libsource (lib "eagle-import") (part "sha2017_rev0_1_0_dev_R0603-DASHES"))
    )
    (comp (ref "TB100")
      (value "TOUCHSELECT")
      (footprint "eagle-import:TOUCH_SELECT")
      (fields (field (name "PARTNO") "NAP"))
      (libsource (lib "eagle-import") (part "TOUCHSELECT"))
    )
    (comp (ref "TB101")
      (value "TOUCHSELECT")
      (footprint "eagle-import:TOUCH_SELECT")
      (fields (field (name "PARTNO") "NAP"))
      (libsource (lib "eagle-import") (part "TOUCHSELECT"))
    )
    (comp (ref "TB102")
      (value "TOUCH_CROSS")
      (footprint "eagle-import:TOUCH_CROSS")
      (fields (field (name "PARTNO") "NAP"))
      (libsource (lib "eagle-import") (part "TOUCH_CROSS"))
    )
    (comp (ref "TB103")
      (value "TOUCHROUND")
      (footprint "eagle-import:TOUCH_BUTTON")
      (fields (field (name "PARTNO") "NAP"))
      (libsource (lib "eagle-import") (part "TOUCHROUND"))
    )
    (comp (ref "TB104")
      (value "TOUCHROUND")
      (footprint "eagle-import:TOUCH_BUTTON")
      (fields (field (name "PARTNO") "NAP"))
      (libsource (lib "eagle-import") (part "TOUCHROUND"))
    )
    (comp (ref "TP1")
      (value "TEST-POINT3")
      (footprint "eagle-import:PAD.03X.03")
      (fields (field (name "PARTNO") "NAP"))
      (libsource (lib "eagle-import") (part "TEST-POINT3"))
    )
    (comp (ref "TP2")
      (value "TEST-POINT3")
      (footprint "eagle-import:PAD.03X.03")
      (fields (field (name "PARTNO") "NAP"))
      (libsource (lib "eagle-import") (part "TEST-POINT3"))
    )
    (comp (ref "TP3")
      (value "TEST-POINT3")
      (footprint "eagle-import:PAD.03X.03")
      (fields (field (name "PARTNO") "NAP"))
      (libsource (lib "eagle-import") (part "TEST-POINT3"))
    )
    (comp (ref "TP100")
      (value "TEST-POINT3")
      (footprint "eagle-import:PAD.03X.03")
      (fields (field (name "PARTNO") "NAP"))
      (libsource (lib "eagle-import") (part "TEST-POINT3"))
    )
    (comp (ref "TP101")
      (value "TEST-POINT3")
      (footprint "eagle-import:PAD.03X.03")
      (fields (field (name "PARTNO") "NAP"))
      (libsource (lib "eagle-import") (part "TEST-POINT3"))
    )
    (comp (ref "U$2")
      (value "VIA")
      (footprint "eagle-import:VIA")
      (fields (field (name "PARTNO") "NAP"))
      (libsource (lib "eagle-import") (part "VIA"))
    )
    (comp (ref "U$3")
      (value "VIA")
      (footprint "eagle-import:VIA")
      (fields (field (name "PARTNO") "NAP"))
      (libsource (lib "eagle-import") (part "VIA"))
    )
    (comp (ref "U$4")
      (value "VIA")
      (footprint "eagle-import:VIA")
      (fields (field (name "PARTNO") "NAP"))
      (libsource (lib "eagle-import") (part "VIA"))
    )
    (comp (ref "U$5")
      (value "VIA")
      (footprint "eagle-import:VIA")
      (fields (field (name "PARTNO") "NAP"))
      (libsource (lib "eagle-import") (part "VIA"))
    )
    (comp (ref "U$6")
      (value "VIA")
      (footprint "eagle-import:VIA")
      (fields (field (name "PARTNO") "NAP"))
      (libsource (lib "eagle-import") (part "VIA"))
    )
    (comp (ref "U$10")
      (value "VIA")
      (footprint "eagle-import:VIA")
      (fields (field (name "PARTNO") "NAP"))
      (libsource (lib "eagle-import") (part "VIA"))
    )
    (comp (ref "U$11")
      (value "VIA")
      (footprint "eagle-import:VIA")
      (fields (field (name "PARTNO") "NAP"))
      (libsource (lib "eagle-import") (part "VIA"))
    )
    (comp (ref "U$12")
      (value "VIA")
      (footprint "eagle-import:VIA")
      (fields (field (name "PARTNO") "NAP"))
      (libsource (lib "eagle-import") (part "VIA"))
    )
    (comp (ref "U$13")
      (value "VIA")
      (footprint "eagle-import:VIA")
      (fields (field (name "PARTNO") "NAP"))
      (libsource (lib "eagle-import") (part "VIA"))
    )
    (comp (ref "U$14")
      (value "VIA")
      (footprint "eagle-import:VIA")
      (fields (field (name "PARTNO") "NAP"))
      (libsource (lib "eagle-import") (part "VIA"))
    )
    (comp (ref "U$15")
      (value "VIA")
      (footprint "eagle-import:VIA")
      (fields (field (name "PARTNO") "NAP"))
      (libsource (lib "eagle-import") (part "VIA"))
    )
    (comp (ref "U$16")
      (value "VIA")
      (footprint "eagle-import:VIA")
      (fields (field (name "PARTNO") "NAP"))
      (libsource (lib "eagle-import") (part "VIA"))
    )
    (comp (ref "U$17")
      (value "VIA")
      (footprint "eagle-import:VIA")
      (fields (field (name "PARTNO") "NAP"))
      (libsource (lib "eagle-import") (part "VIA"))
    )
    (comp (ref "U$18")
      (value "VIA")
      (footprint "eagle-import:VIA")
      (fields (field (name "PARTNO") "NAP"))
      (libsource (lib "eagle-import") (part "VIA"))
    )
    (comp (ref "U$19")
      (value "VIA")
      (footprint "eagle-import:VIA")
      (fields (field (name "PARTNO") "NAP"))
      (libsource (lib "eagle-import") (part "VIA"))
    )
    (comp (ref "U$20")
      (value "VIA")
      (footprint "eagle-import:VIA")
      (fields (field (name "PARTNO") "NAP"))
      (libsource (lib "eagle-import") (part "VIA"))
    )
    (comp (ref "U$21")
      (value "VIA")
      (footprint "eagle-import:VIA")
      (fields (field (name "PARTNO") "NAP"))
      (libsource (lib "eagle-import") (part "VIA"))
    )
    (comp (ref "U$22")
      (value "VIA")
      (footprint "eagle-import:VIA")
      (fields (field (name "PARTNO") "NAP"))
      (libsource (lib "eagle-import") (part "VIA"))
    )
    (comp (ref "U$23")
      (value "VIA")
      (footprint "eagle-import:VIA")
      (fields (field (name "PARTNO") "NAP"))
      (libsource (lib "eagle-import") (part "VIA"))
    )
    (comp (ref "C1")
      (value "100n")
      (footprint "eagle-import:C0603-DASHES")
      (fields (field (name "PARTNO") "GRM188R71H104KA93D"))
      (libsource (lib "eagle-import") (part "C0603-DASHES"))
    )
    (comp (ref "C2")
      (value "100n")
      (footprint "eagle-import:C0603-DASHES")
      (fields (field (name "PARTNO") "GRM188R71H104KA93D"))
      (libsource (lib "eagle-import") (part "C0603-DASHES"))
    )
    (comp (ref "C3")
      (value "100n")
      (footprint "eagle-import:C0603-DASHES")
      (fields (field (name "PARTNO") "GRM188R71H104KA93D"))
      (libsource (lib "eagle-import") (part "C0603-DASHES"))
    )
    (comp (ref "C4")
      (value "100n")
      (footprint "eagle-import:C0603-DASHES")
      (fields (field (name "PARTNO") "GRM188R71H104KA93D"))
      (libsource (lib "eagle-import") (part "C0603-DASHES"))
    )
    (comp (ref "C5")
      (value "100n")
      (footprint "eagle-import:C0603-DASHES")
      (fields (field (name "PARTNO") "GRM188R71H104KA93D"))
      (libsource (lib "eagle-import") (part "C0603-DASHES"))
    )
    (comp (ref "C6")
      (value "100n")
      (footprint "eagle-import:C0603-DASHES")
      (fields (field (name "PARTNO") "GRM188R71H104KA93D"))
      (libsource (lib "eagle-import") (part "C0603-DASHES"))
    )
    (comp (ref "C13")
      (value "4u7/16V")
      (footprint "eagle-import:C0805")
      (fields (field (name "PARTNO") "GRM21BR61C475KA88K"))
      (libsource (lib "eagle-import") (part "C-EUC0805"))
    )
    (comp (ref "D100")
      (value "SK6812")
      (footprint "eagle-import:WS2812B")
      (libsource (lib "eagle-import") (part "WS2812B"))
    )
    (comp (ref "D101")
      (value "SK6812")
      (footprint "eagle-import:WS2812B")
      (libsource (lib "eagle-import") (part "WS2812B"))
    )
    (comp (ref "D102")
      (value "SK6812")
      (footprint "eagle-import:WS2812B")
      (libsource (lib "eagle-import") (part "WS2812B"))
    )
    (comp (ref "D103")
      (value "SK6812")
      (footprint "eagle-import:WS2812B")
      (libsource (lib "eagle-import") (part "WS2812B"))
    )
    (comp (ref "D104")
      (value "SK6812")
      (footprint "eagle-import:WS2812B")
      (libsource (lib "eagle-import") (part "WS2812B"))
    )
    (comp (ref "D105")
      (value "SK6812")
      (footprint "eagle-import:WS2812B")
      (libsource (lib "eagle-import") (part "WS2812B"))
    )
    (comp (ref "Q1")
      (value "MMBT2222A")
      (footprint "eagle-import:SOT23-3")
      (fields (field (name "PARTNO") "BC817-25,215"))
      (libsource (lib "eagle-import") (part "TRANSISTOR_NPNMMBT2222A"))
    )
    (comp (ref "R9")
      (value "10k")
      (footprint "eagle-import:R0603-DASHES")
      (fields (field (name "PARTNO") "ERJ-3GEYJ103V"))
      (libsource (lib "eagle-import") (part "R0603-DASHES"))
    )
    (comp (ref "R10")
      (value "10k")
      (footprint "eagle-import:R0603-DASHES")
      (fields (field (name "PARTNO") "ERJ-3GEYJ103V"))
      (libsource (lib "eagle-import") (part "R0603-DASHES"))
    )
    (comp (ref "T2")
      (value "MOSFET-PCHANNEL")
      (footprint "eagle-import:SOT23-3")
      (libsource (lib "eagle-import") (part "MOSFET-PCHANNEL"))
    )
  )
  (nets
    (net (code "1") (name "+3V3") (class "Default")
      (node (ref "C17") (pin "1") (pinfunction "1_1") (pintype "passive"))
      (node (ref "C20") (pin "1") (pinfunction "1_1") (pintype "passive"))
      (node (ref "C22") (pin "1") (pinfunction "1_1") (pintype "passive"))
      (node (ref "C26") (pin "1") (pinfunction "1_1") (pintype "passive"))
      (node (ref "C27") (pin "1") (pinfunction "1_1") (pintype "passive"))
      (node (ref "C30") (pin "1") (pinfunction "1_1") (pintype "passive"))
      (node (ref "C37") (pin "1") (pinfunction "1_1") (pintype "passive"))
      (node (ref "C39") (pin "1") (pinfunction "1_1") (pintype "passive"))
      (node (ref "C42") (pin "1") (pinfunction "1_1") (pintype "passive"))
      (node (ref "C43") (pin "1") (pinfunction "1_1") (pintype "passive"))
      (node (ref "C44") (pin "1") (pinfunction "1_1") (pintype "passive"))
      (node (ref "IC2") (pin "3") (pinfunction "OUT_3") (pintype "passive"))
      (node (ref "IC3") (pin "2") (pinfunction "VCC_2") (pintype "power_in"))
      (node (ref "IC5") (pin "15") (pinfunction "VCC_15") (pintype "bidirectional"))
      (node (ref "IC5") (pin "2") (pinfunction "VDDIO_2") (pintype "bidirectional"))
      (node (ref "IC5") (pin "9") (pinfunction "ADDR_9") (pintype "bidirectional"))
      (node (ref "IC6") (pin "4") (pinfunction "VDD_4") (pintype "bidirectional"))
      (node (ref "L1") (pin "1") (pinfunction "1_1") (pintype "passive"))
      (node (ref "R16") (pin "2") (pinfunction "2_2") (pintype "passive"))
      (node (ref "R22") (pin "1") (pinfunction "1_1") (pintype "passive"))
      (node (ref "R23") (pin "1") (pinfunction "1_1") (pintype "passive"))
      (node (ref "R24") (pin "1") (pinfunction "1_1") (pintype "passive"))
      (node (ref "R28") (pin "2") (pinfunction "2_2") (pintype "passive"))
      (node (ref "R33") (pin "1") (pinfunction "1_1") (pintype "passive"))
      (node (ref "R34") (pin "2") (pinfunction "2_2") (pintype "passive"))
      (node (ref "T3") (pin "2") (pinfunction "S_2") (pintype "passive"))
      (node (ref "TP119") (pin "P$1") (pinfunction "1_P$1") (pintype "bidirectional"))
      (node (ref "X1") (pin "10") (pinfunction "10_10") (pintype "passive"))
      (node (ref "X1") (pin "7") (pinfunction "7_7") (pintype "passive"))
      (node (ref "X1") (pin "9") (pinfunction "9_9") (pintype "passive"))
    )
    (net (code "2") (name "+5V") (class "Default")
      (node (ref "C11") (pin "1") (pinfunction "1_1") (pintype "passive"))
      (node (ref "C23") (pin "2") (pinfunction "2_2") (pintype "passive"))
      (node (ref "C24") (pin "1") (pinfunction "1_1") (pintype "passive"))
      (node (ref "C9") (pin "1") (pinfunction "1_1") (pintype "passive"))
      (node (ref "D1") (pin "C") (pinfunction "C_C") (pintype "passive"))
      (node (ref "D3") (pin "A") (pinfunction "A_A") (pintype "passive"))
      (node (ref "F1") (pin "2") (pinfunction "2_2") (pintype "bidirectional"))
      (node (ref "IC1") (pin "7") (pinfunction "REGIN_7") (pintype "passive"))
      (node (ref "IC1") (pin "8") (pinfunction "VBUS_8") (pintype "input"))
      (node (ref "IC4") (pin "1") (pinfunction "VDD_1") (pintype "bidirectional"))
      (node (ref "IC4") (pin "2") (pinfunction "VDD_2") (pintype "bidirectional"))
      (node (ref "R4") (pin "2") (pinfunction "2_2") (pintype "passive"))
      (node (ref "R7") (pin "2") (pinfunction "2_2") (pintype "passive"))
      (node (ref "T1") (pin "1") (pinfunction "G_1") (pintype "passive"))
      (node (ref "TP112") (pin "P$1") (pinfunction "1_P$1") (pintype "bidirectional"))
    )
    (net (code "3") (name "3V3_SWITCHED") (class "Default")
      (node (ref "C12") (pin "1") (pinfunction "1_1") (pintype "passive"))
      (node (ref "C31") (pin "1") (pinfunction "1_1") (pintype "passive"))
      (node (ref "C40") (pin "1") (pinfunction "1_1") (pintype "passive"))
      (node (ref "C41") (pin "1") (pinfunction "1_1") (pintype "passive"))
      (node (ref "C7") (pin "1") (pinfunction "1_1") (pintype "passive"))
      (node (ref "R1") (pin "2") (pinfunction "2_2") (pintype "passive"))
      (node (ref "R17") (pin "2") (pinfunction "2_2") (pintype "passive"))
      (node (ref "R25") (pin "2") (pinfunction "2_2") (pintype "passive"))
      (node (ref "R26") (pin "2") (pinfunction "2_2") (pintype "passive"))
      (node (ref "R31") (pin "1") (pinfunction "1_1") (pintype "passive"))
      (node (ref "R5") (pin "2") (pinfunction "2_2") (pintype "passive"))
      (node (ref "R8") (pin "2") (pinfunction "2_2") (pintype "passive"))
      (node (ref "T3") (pin "3") (pinfunction "D_3") (pintype "passive"))
      (node (ref "TP116") (pin "P$1") (pinfunction "1_P$1") (pintype "bidirectional"))
      (node (ref "X2") (pin "4") (pinfunction "VCC_4") (pintype "bidirectional"))
      (node (ref "X3") (pin "12") (pinfunction "1_12") (pintype "passive"))
    )
    (net (code "4") (name "CHRG_STAT") (class "Default")
      (node (ref "IC4") (pin "3") (pinfunction "STAT1_3") (pintype "bidirectional"))
      (node (ref "IC5") (pin "12") (pinfunction "GPIO0_12") (pintype "bidirectional"))
    )
    (net (code "5") (name "ESP32_FLASH") (class "Default")
      (node (ref "D2") (pin "C") (pinfunction "C_C") (pintype "passive"))
      (node (ref "IC3") (pin "25") (pinfunction "IO0_25") (pintype "bidirectional"))
      (node (ref "Q4") (pin "3") (pinfunction "C_3") (pintype "passive"))
      (node (ref "R16") (pin "1") (pinfunction "1_1") (pintype "passive"))
      (node (ref "S2") (pin "3") (pinfunction "2_3") (pintype "passive"))
      (node (ref "TP120") (pin "P$1") (pinfunction "1_P$1") (pintype "bidirectional"))
    )
    (net (code "6") (name "ESP32_RX") (class "Default")
      (node (ref "D4") (pin "C") (pinfunction "C_C") (pintype "passive"))
      (node (ref "IC1") (pin "26") (pinfunction "TXD_26") (pintype "output"))
      (node (ref "IC3") (pin "34") (pinfunction "RXD0_34") (pintype "bidirectional"))
      (node (ref "TP133") (pin "P$1") (pinfunction "1_P$1") (pintype "bidirectional"))
    )
    (net (code "7") (name "ESP32_TX") (class "Default")
      (node (ref "D5") (pin "C") (pinfunction "C_C") (pintype "passive"))
      (node (ref "IC1") (pin "25") (pinfunction "RXD_25") (pintype "input"))
      (node (ref "IC3") (pin "35") (pinfunction "TXD0_35") (pintype "bidirectional"))
      (node (ref "TP134") (pin "P$1") (pinfunction "1_P$1") (pintype "bidirectional"))
    )
    (net (code "8") (name "ESP32_~{RESET}") (class "Default")
      (node (ref "IC3") (pin "3") (pinfunction "EN_3") (pintype "bidirectional"))
      (node (ref "Q3") (pin "3") (pinfunction "C_3") (pintype "passive"))
      (node (ref "R22") (pin "2") (pinfunction "2_2") (pintype "passive"))
      (node (ref "S1") (pin "3") (pinfunction "2_3") (pintype "passive"))
      (node (ref "TP121") (pin "P$1") (pinfunction "1_P$1") (pintype "bidirectional"))
    )
    (net (code "9") (name "EXTIO-0") (class "Default")
      (node (ref "IC3") (pin "9") (pinfunction "IO33_9") (pintype "bidirectional"))
      (node (ref "X3") (pin "3") (pinfunction "10_3") (pintype "passive"))
    )
    (net (code "10") (name "EXTIO-1") (class "Default")
      (node (ref "IC3") (pin "27") (pinfunction "IO16_27") (pintype "bidirectional"))
      (node (ref "X3") (pin "4") (pinfunction "9_4") (pintype "passive"))
    )
    (net (code "11") (name "EXTIO-2") (class "Default")
      (node (ref "IC3") (pin "28") (pinfunction "IO17_28") (pintype "bidirectional"))
      (node (ref "X3") (pin "5") (pinfunction "8_5") (pintype "passive"))
    )
    (net (code "12") (name "EXTIO-3") (class "Default")
      (node (ref "IC5") (pin "3") (pinfunction "GPIO7_3") (pintype "bidirectional"))
      (node (ref "X3") (pin "9") (pinfunction "4_9") (pintype "passive"))
    )
    (net (code "13") (name "EXTIO-4") (class "Default")
      (node (ref "IC5") (pin "4") (pinfunction "GPIO6_4") (pintype "bidirectional"))
      (node (ref "X3") (pin "10") (pinfunction "3_10") (pintype "passive"))
    )
    (net (code "14") (name "EXTIO-5") (class "Default")
      (node (ref "IC5") (pin "5") (pinfunction "GPIO5_5") (pintype "bidirectional"))
      (node (ref "X3") (pin "11") (pinfunction "2_11") (pintype "passive"))
    )
    (net (code "15") (name "GDR") (class "Default")
      (node (ref "Q5") (pin "1") (pinfunction "G_1") (pintype "passive"))
      (node (ref "TP124") (pin "P$1") (pinfunction "1_P$1") (pintype "bidirectional"))
      (node (ref "X1") (pin "23") (pinfunction "23_23") (pintype "passive"))
    )
    (net (code "16") (name "GND") (class "Default")
      (node (ref "$$U$1") (pin "P$1") (pinfunction "P$1_P$1") (pintype "bidirectional"))
      (node (ref "$$U$2") (pin "P$1") (pinfunction "P$1_P$1") (pintype "bidirectional"))
      (node (ref "$$U$3") (pin "P$1") (pinfunction "P$1_P$1") (pintype "bidirectional"))
      (node (ref "$$U$4") (pin "P$1") (pinfunction "P$1_P$1") (pintype "bidirectional"))
      (node (ref "$$U$5") (pin "P$1") (pinfunction "P$1_P$1") (pintype "bidirectional"))
      (node (ref "$$U$6") (pin "P$1") (pinfunction "P$1_P$1") (pintype "bidirectional"))
      (node (ref "$$U$7") (pin "P$1") (pinfunction "P$1_P$1") (pintype "bidirectional"))
      (node (ref "$$U$8") (pin "P$1") (pinfunction "P$1_P$1") (pintype "bidirectional"))
      (node (ref "$$U$9") (pin "P$1") (pinfunction "P$1_P$1") (pintype "bidirectional"))
      (node (ref "C1") (pin "1") (pinfunction "1_1") (pintype "passive"))
      (node (ref "C10") (pin "2") (pinfunction "2_2") (pintype "passive"))
      (node (ref "C11") (pin "2") (pinfunction "2_2") (pintype "passive"))
      (node (ref "C12") (pin "2") (pinfunction "2_2") (pintype "passive"))
      (node (ref "C13") (pin "2") (pinfunction "2_2") (pintype "passive"))
      (node (ref "C14") (pin "2") (pinfunction "2_2") (pintype "passive"))
      (node (ref "C15") (pin "2") (pinfunction "2_2") (pintype "passive"))
      (node (ref "C16") (pin "2") (pinfunction "2_2") (pintype "passive"))
      (node (ref "C17") (pin "2") (pinfunction "2_2") (pintype "passive"))
      (node (ref "C18") (pin "2") (pinfunction "2_2") (pintype "passive"))
      (node (ref "C19") (pin "1") (pinfunction "1_1") (pintype "passive"))
      (node (ref "C2") (pin "1") (pinfunction "1_1") (pintype "passive"))
      (node (ref "C20") (pin "2") (pinfunction "2_2") (pintype "passive"))
      (node (ref "C21") (pin "1") (pinfunction "1_1") (pintype "passive"))
      (node (ref "C22") (pin "2") (pinfunction "2_2") (pintype "passive"))
      (node (ref "C23") (pin "1") (pinfunction "1_1") (pintype "passive"))
      (node (ref "C24") (pin "2") (pinfunction "2_2") (pintype "passive"))
      (node (ref "C26") (pin "2") (pinfunction "2_2") (pintype "passive"))
      (node (ref "C27") (pin "2") (pinfunction "2_2") (pintype "passive"))
      (node (ref "C28") (pin "1") (pinfunction "1_1") (pintype "passive"))
      (node (ref "C29") (pin "1") (pinfunction "1_1") (pintype "passive"))
      (node (ref "C3") (pin "1") (pinfunction "1_1") (pintype "passive"))
      (node (ref "C30") (pin "2") (pinfunction "2_2") (pintype "passive"))
      (node (ref "C31") (pin "2") (pinfunction "2_2") (pintype "passive"))
      (node (ref "C32") (pin "1") (pinfunction "1_1") (pintype "passive"))
      (node (ref "C33") (pin "1") (pinfunction "1_1") (pintype "passive"))
      (node (ref "C34") (pin "2") (pinfunction "2_2") (pintype "passive"))
      (node (ref "C35") (pin "1") (pinfunction "1_1") (pintype "passive"))
      (node (ref "C36") (pin "1") (pinfunction "1_1") (pintype "passive"))
      (node (ref "C37") (pin "2") (pinfunction "2_2") (pintype "passive"))
      (node (ref "C38") (pin "1") (pinfunction "1_1") (pintype "passive"))
      (node (ref "C39") (pin "2") (pinfunction "2_2") (pintype "passive"))
      (node (ref "C4") (pin "1") (pinfunction "1_1") (pintype "passive"))
      (node (ref "C40") (pin "2") (pinfunction "2_2") (pintype "passive"))
      (node (ref "C41") (pin "2") (pinfunction "2_2") (pintype "passive"))
      (node (ref "C42") (pin "2") (pinfunction "2_2") (pintype "passive"))
      (node (ref "C43") (pin "2") (pinfunction "2_2") (pintype "passive"))
      (node (ref "C44") (pin "2") (pinfunction "2_2") (pintype "passive"))
      (node (ref "C5") (pin "1") (pinfunction "1_1") (pintype "passive"))
      (node (ref "C6") (pin "1") (pinfunction "1_1") (pintype "passive"))
      (node (ref "C7") (pin "2") (pinfunction "2_2") (pintype "passive"))
      (node (ref "C8") (pin "2") (pinfunction "2_2") (pintype "passive"))
      (node (ref "C9") (pin "2") (pinfunction "2_2") (pintype "passive"))
      (node (ref "D1") (pin "A") (pinfunction "A_A") (pintype "passive"))
      (node (ref "D100") (pin "3") (pinfunction "VSS_3") (pintype "power_in"))
      (node (ref "D101") (pin "3") (pinfunction "VSS_3") (pintype "power_in"))
      (node (ref "D102") (pin "3") (pinfunction "VSS_3") (pintype "power_in"))
      (node (ref "D103") (pin "3") (pinfunction "VSS_3") (pintype "power_in"))
      (node (ref "D104") (pin "3") (pinfunction "VSS_3") (pintype "power_in"))
      (node (ref "D105") (pin "3") (pinfunction "VSS_3") (pintype "power_in"))
      (node (ref "D6") (pin "C") (pinfunction "C_C") (pintype "passive"))
      (node (ref "D7") (pin "C") (pinfunction "C_C") (pintype "passive"))
      (node (ref "IC1") (pin "3") (pinfunction "GND_3") (pintype "power_in"))
      (node (ref "IC1") (pin "EXP") (pinfunction "GND_EXP") (pintype "power_in"))
      (node (ref "IC1") (pin "M") (pinfunction "GND_M") (pintype "power_in"))
      (node (ref "IC2") (pin "1") (pinfunction "GND_1") (pintype "input"))
      (node (ref "IC3") (pin "0") (pinfunction "GND_0") (pintype "power_in"))
      (node (ref "IC3") (pin "1") (pinfunction "GND_1") (pintype "power_in"))
      (node (ref "IC3") (pin "15") (pinfunction "GND_15") (pintype "power_in"))
      (node (ref "IC3") (pin "38") (pinfunction "GND_38") (pintype "power_in"))
      (node (ref "IC4") (pin "5") (pinfunction "VSS_5") (pintype "bidirectional"))
      (node (ref "IC5") (pin "16") (pinfunction "GND_16") (pintype "bidirectional"))
      (node (ref "IC6") (pin "12") (pinfunction "GND_12") (pintype "bidirectional"))
      (node (ref "IC6") (pin "3") (pinfunction "GND_3") (pintype "bidirectional"))
      (node (ref "Q1") (pin "2") (pinfunction "E_2") (pintype "passive"))
      (node (ref "Q2") (pin "2") (pinfunction "E_2") (pintype "passive"))
      (node (ref "Q6") (pin "2") (pinfunction "E_2") (pintype "passive"))
      (node (ref "R19") (pin "2") (pinfunction "2_2") (pintype "passive"))
      (node (ref "R20") (pin "1") (pinfunction "1_1") (pintype "passive"))
      (node (ref "R29") (pin "1") (pinfunction "1_1") (pintype "passive"))
      (node (ref "R32") (pin "1") (pinfunction "1_1") (pintype "passive"))
      (node (ref "R4") (pin "1") (pinfunction "1_1") (pintype "passive"))
      (node (ref "R6") (pin "1") (pinfunction "1_1") (pintype "passive"))
      (node (ref "S1") (pin "1") (pinfunction "1_1") (pintype "passive"))
      (node (ref "S2") (pin "1") (pinfunction "1_1") (pintype "passive"))
      (node (ref "TP1") (pin "P$1") (pinfunction "1_P$1") (pintype "bidirectional"))
      (node (ref "TP102") (pin "P$1") (pinfunction "1_P$1") (pintype "bidirectional"))
      (node (ref "TP103") (pin "P$1") (pinfunction "1_P$1") (pintype "bidirectional"))
      (node (ref "TP106") (pin "P$1") (pinfunction "1_P$1") (pintype "bidirectional"))
      (node (ref "TP122") (pin "P$1") (pinfunction "1_P$1") (pintype "bidirectional"))
      (node (ref "TP125") (pin "P$1") (pinfunction "1_P$1") (pintype "bidirectional"))
      (node (ref "TP135") (pin "P$1") (pinfunction "1_P$1") (pintype "bidirectional"))
      (node (ref "TP140") (pin "P$1") (pinfunction "1_P$1") (pintype "bidirectional"))
      (node (ref "U$10") (pin "P$1") (pinfunction "P$1_P$1") (pintype "bidirectional"))
      (node (ref "U$11") (pin "P$1") (pinfunction "P$1_P$1") (pintype "bidirectional"))
      (node (ref "U$12") (pin "P$1") (pinfunction "P$1_P$1") (pintype "bidirectional"))
      (node (ref "U$13") (pin "P$1") (pinfunction "P$1_P$1") (pintype "bidirectional"))
      (node (ref "U$14") (pin "P$1") (pinfunction "P$1_P$1") (pintype "bidirectional"))
      (node (ref "U$15") (pin "P$1") (pinfunction "P$1_P$1") (pintype "bidirectional"))
      (node (ref "U$16") (pin "P$1") (pinfunction "P$1_P$1") (pintype "bidirectional"))
      (node (ref "U$17") (pin "P$1") (pinfunction "P$1_P$1") (pintype "bidirectional"))
      (node (ref "U$18") (pin "P$1") (pinfunction "P$1_P$1") (pintype "bidirectional"))
      (node (ref "U$19") (pin "P$1") (pinfunction "P$1_P$1") (pintype "bidirectional"))
      (node (ref "U$2") (pin "P$1") (pinfunction "P$1_P$1") (pintype "bidirectional"))
      (node (ref "U$20") (pin "P$1") (pinfunction "P$1_P$1") (pintype "bidirectional"))
      (node (ref "U$21") (pin "P$1") (pinfunction "P$1_P$1") (pintype "bidirectional"))
      (node (ref "U$22") (pin "P$1") (pinfunction "P$1_P$1") (pintype "bidirectional"))
      (node (ref "U$23") (pin "P$1") (pinfunction "P$1_P$1") (pintype "bidirectional"))
      (node (ref "U$3") (pin "P$1") (pinfunction "P$1_P$1") (pintype "bidirectional"))
      (node (ref "U$4") (pin "P$1") (pinfunction "P$1_P$1") (pintype "bidirectional"))
      (node (ref "U$5") (pin "P$1") (pinfunction "P$1_P$1") (pintype "bidirectional"))
      (node (ref "U$6") (pin "P$1") (pinfunction "P$1_P$1") (pintype "bidirectional"))
      (node (ref "USB1") (pin "5") (pinfunction "5_5") (pintype "input"))
      (node (ref "USB1") (pin "GND1") (pinfunction "GND1_GND1") (pintype "bidirectional"))
      (node (ref "USB1") (pin "GND2") (pinfunction "GND2_GND2") (pintype "bidirectional"))
      (node (ref "USB1") (pin "GND3") (pinfunction "GND3_GND3") (pintype "bidirectional"))
      (node (ref "USB1") (pin "GND4") (pinfunction "GND4_GND4") (pintype "bidirectional"))
      (node (ref "X1") (pin "17") (pinfunction "17_17") (pintype "passive"))
      (node (ref "X1") (pin "8") (pinfunction "8_8") (pintype "passive"))
      (node (ref "X2") (pin "6") (pinfunction "GND_6") (pintype "bidirectional"))
      (node (ref "X2") (pin "CD2") (pinfunction "SHIELD_CD2") (pintype "bidirectional"))
      (node (ref "X2") (pin "GND1") (pinfunction "SHIELD_GND1") (pintype "bidirectional"))
      (node (ref "X2") (pin "GND3") (pinfunction "SHIELD_GND3") (pintype "bidirectional"))
      (node (ref "X3") (pin "1") (pinfunction "12_1") (pintype "passive"))
      (node (ref "X4") (pin "2") (pinfunction "1_2") (pintype "passive"))
    )
    (net (code "17") (name "I2C_INT") (class "Default")
      (node (ref "IC3") (pin "10") (pinfunction "IO25_10") (pintype "bidirectional"))
      (node (ref "IC5") (pin "1") (pinfunction "INT_1") (pintype "bidirectional"))
    )
    (net (code "18") (name "I2C_SCL") (class "Default")
      (node (ref "IC3") (pin "12") (pinfunction "IO27_12") (pintype "bidirectional"))
      (node (ref "IC5") (pin "13") (pinfunction "SCL_13") (pintype "bidirectional"))
      (node (ref "IC6") (pin "8") (pinfunction "EB_SCL_8") (pintype "bidirectional"))
      (node (ref "R24") (pin "2") (pinfunction "2_2") (pintype "passive"))
      (node (ref "TP114") (pin "P$1") (pinfunction "1_P$1") (pintype "bidirectional"))
      (node (ref "X3") (pin "6") (pinfunction "7_6") (pintype "passive"))
    )
    (net (code "19") (name "I2C_SDA") (class "Default")
      (node (ref "IC3") (pin "11") (pinfunction "IO26_11") (pintype "bidirectional"))
      (node (ref "IC5") (pin "14") (pinfunction "SDA_14") (pintype "bidirectional"))
      (node (ref "IC6") (pin "9") (pinfunction "EB_SDA_9") (pintype "bidirectional"))
      (node (ref "R23") (pin "2") (pinfunction "2_2") (pintype "passive"))
      (node (ref "TP115") (pin "P$1") (pinfunction "1_P$1") (pintype "bidirectional"))
      (node (ref "X3") (pin "7") (pinfunction "6_7") (pintype "passive"))
    )
    (net (code "20") (name "LCD_BUSY") (class "Default")
      (node (ref "IC3") (pin "36") (pinfunction "IO22_36") (pintype "bidirectional"))
      (node (ref "TP118") (pin "P$1") (pinfunction "1_P$1") (pintype "bidirectional"))
      (node (ref "X1") (pin "16") (pinfunction "16_16") (pintype "passive"))
    )
    (net (code "21") (name "LCD_CS") (class "Default")
      (node (ref "IC3") (pin "31") (pinfunction "IO19_31") (pintype "bidirectional"))
      (node (ref "TP109") (pin "P$1") (pinfunction "1_P$1") (pintype "bidirectional"))
      (node (ref "X1") (pin "13") (pinfunction "13_13") (pintype "passive"))
    )
    (net (code "22") (name "LCD_D{slash}~{S}") (class "Default")
      (node (ref "IC3") (pin "33") (pinfunction "IO21_33") (pintype "bidirectional"))
      (node (ref "TP111") (pin "P$1") (pinfunction "1_P$1") (pintype "bidirectional"))
      (node (ref "X1") (pin "14") (pinfunction "14_14") (pintype "passive"))
    )
    (net (code "23") (name "LCD_MOSI") (class "Default")
      (node (ref "IC3") (pin "29") (pinfunction "IO5_29") (pintype "bidirectional"))
      (node (ref "TP107") (pin "P$1") (pinfunction "1_P$1") (pintype "bidirectional"))
      (node (ref "X1") (pin "11") (pinfunction "11_11") (pintype "passive"))
    )
    (net (code "24") (name "LCD_SCK") (class "Default")
      (node (ref "IC3") (pin "30") (pinfunction "IO18_30") (pintype "bidirectional"))
      (node (ref "TP108") (pin "P$1") (pinfunction "1_P$1") (pintype "bidirectional"))
      (node (ref "X1") (pin "12") (pinfunction "12_12") (pintype "passive"))
    )
    (net (code "25") (name "LCD_~{RESET}") (class "Default")
      (node (ref "IC3") (pin "37") (pinfunction "IO23_37") (pintype "bidirectional"))
      (node (ref "TP113") (pin "P$1") (pinfunction "1_P$1") (pintype "bidirectional"))
      (node (ref "X1") (pin "15") (pinfunction "15_15") (pintype "passive"))
    )
    (net (code "26") (name "Net-(C25-Pad1)") (class "Default")
      (node (ref "C25") (pin "1") (pinfunction "1_1") (pintype "passive"))
      (node (ref "D7") (pin "A") (pinfunction "A_A") (pintype "passive"))
      (node (ref "D8") (pin "C") (pinfunction "C_C") (pintype "passive"))
    )
    (net (code "27") (name "Net-(D4-PadA)") (class "Default")
      (node (ref "D4") (pin "A") (pinfunction "A_A") (pintype "passive"))
      (node (ref "R3") (pin "1") (pinfunction "1_1") (pintype "passive"))
    )
    (net (code "28") (name "Net-(D5-PadA)") (class "Default")
      (node (ref "D5") (pin "A") (pinfunction "A_A") (pintype "passive"))
      (node (ref "R14") (pin "1") (pinfunction "1_1") (pintype "passive"))
    )
    (net (code "29") (name "Net-(D6-PadA)") (class "Default")
      (node (ref "D6") (pin "A") (pinfunction "A_A") (pintype "passive"))
      (node (ref "R12") (pin "1") (pinfunction "1_1") (pintype "passive"))
    )
    (net (code "30") (name "Net-(D100-DIN)") (class "Default")
      (node (ref "D100") (pin "4") (pinfunction "DIN_4") (pintype "input"))
      (node (ref "D101") (pin "2") (pinfunction "DOUT_2") (pintype "output"))
    )
    (net (code "31") (name "Net-(D101-DIN)") (class "Default")
      (node (ref "D101") (pin "4") (pinfunction "DIN_4") (pintype "input"))
      (node (ref "D102") (pin "2") (pinfunction "DOUT_2") (pintype "output"))
    )
    (net (code "32") (name "Net-(D102-DIN)") (class "Default")
      (node (ref "D102") (pin "4") (pinfunction "DIN_4") (pintype "input"))
      (node (ref "D103") (pin "2") (pinfunction "DOUT_2") (pintype "output"))
    )
    (net (code "33") (name "Net-(D103-DIN)") (class "Default")
      (node (ref "D103") (pin "4") (pinfunction "DIN_4") (pintype "input"))
      (node (ref "D104") (pin "2") (pinfunction "DOUT_2") (pintype "output"))
    )
    (net (code "34") (name "Net-(D104-DIN)") (class "Default")
      (node (ref "D104") (pin "4") (pinfunction "DIN_4") (pintype "input"))
      (node (ref "D105") (pin "2") (pinfunction "DOUT_2") (pintype "output"))
    )
    (net (code "35") (name "Net-(IC1-DTR)") (class "Default")
      (node (ref "IC1") (pin "28") (pinfunction "DTR_28") (pintype "output"))
      (node (ref "Q4") (pin "2") (pinfunction "E_2") (pintype "passive"))
      (node (ref "R18") (pin "1") (pinfunction "1_1") (pintype "passive"))
    )
    (net (code "36") (name "Net-(IC1-RTS)") (class "Default")
      (node (ref "IC1") (pin "24") (pinfunction "RTS_24") (pintype "output"))
      (node (ref "Q3") (pin "2") (pinfunction "E_2") (pintype "passive"))
      (node (ref "R15") (pin "1") (pinfunction "1_1") (pintype "passive"))
    )
    (net (code "37") (name "Net-(IC1-~{RST})") (class "Default")
      (node (ref "IC1") (pin "9") (pinfunction "~{RST}_9") (pintype "bidirectional"))
      (node (ref "R13") (pin "2") (pinfunction "2_2") (pintype "passive"))
    )
    (net (code "38") (name "Net-(IC3-CLK)") (class "Default")
      (node (ref "IC3") (pin "20") (pinfunction "CLK_20") (pintype "bidirectional"))
      (node (ref "TP130") (pin "P$1") (pinfunction "1_P$1") (pintype "bidirectional"))
    )
    (net (code "39") (name "Net-(IC3-CND)") (class "Default")
      (node (ref "IC3") (pin "19") (pinfunction "CND_19") (pintype "bidirectional"))
      (node (ref "TP128") (pin "P$1") (pinfunction "1_P$1") (pintype "bidirectional"))
    )
    (net (code "40") (name "Net-(IC3-SD0)") (class "Default")
      (node (ref "IC3") (pin "21") (pinfunction "SD0_21") (pintype "bidirectional"))
      (node (ref "TP131") (pin "P$1") (pinfunction "1_P$1") (pintype "bidirectional"))
    )
    (net (code "41") (name "Net-(IC3-SD1)") (class "Default")
      (node (ref "IC3") (pin "22") (pinfunction "SD1_22") (pintype "bidirectional"))
      (node (ref "TP132") (pin "P$1") (pinfunction "1_P$1") (pintype "bidirectional"))
    )
    (net (code "42") (name "Net-(IC3-SD2)") (class "Default")
      (node (ref "IC3") (pin "17") (pinfunction "SD2_17") (pintype "bidirectional"))
      (node (ref "TP126") (pin "P$1") (pinfunction "1_P$1") (pintype "bidirectional"))
    )
    (net (code "43") (name "Net-(IC3-SD3)") (class "Default")
      (node (ref "IC3") (pin "18") (pinfunction "SD3_18") (pintype "bidirectional"))
      (node (ref "TP127") (pin "P$1") (pinfunction "1_P$1") (pintype "bidirectional"))
    )
    (net (code "44") (name "Net-(IC3-SENSOR_VN)") (class "Default")
      (node (ref "C29") (pin "2") (pinfunction "2_2") (pintype "passive"))
      (node (ref "IC3") (pin "5") (pinfunction "SENSOR_VN_5") (pintype "bidirectional"))
    )
    (net (code "45") (name "Net-(IC3-SENSOR_VP)") (class "Default")
      (node (ref "C28") (pin "2") (pinfunction "2_2") (pintype "passive"))
      (node (ref "IC3") (pin "4") (pinfunction "SENSOR_VP_4") (pintype "bidirectional"))
    )
    (net (code "46") (name "Net-(IC4-PROG)") (class "Default")
      (node (ref "IC4") (pin "6") (pinfunction "PROG_6") (pintype "bidirectional"))
      (node (ref "R29") (pin "2") (pinfunction "2_2") (pintype "passive"))
    )
    (net (code "47") (name "Net-(IC4-THERM)") (class "Default")
      (node (ref "IC4") (pin "8") (pinfunction "THERM_8") (pintype "bidirectional"))
      (node (ref "R30") (pin "2") (pinfunction "2_2") (pintype "passive"))
    )
    (net (code "48") (name "Net-(IC5-~{RESET})") (class "Default")
      (node (ref "IC5") (pin "10") (pinfunction "~{RESET}_10") (pintype "bidirectional"))
      (node (ref "R33") (pin "2") (pinfunction "2_2") (pintype "passive"))
    )
    (net (code "49") (name "Net-(IC6-CONF_CLK{slash}RST)") (class "Default")
      (node (ref "IC6") (pin "5") (pinfunction "CONF_CLK/RST_5") (pintype "bidirectional"))
      (node (ref "R34") (pin "1") (pinfunction "1_1") (pintype "passive"))
      (node (ref "TP100") (pin "P$1") (pinfunction "1_P$1") (pintype "bidirectional"))
      (node (ref "TP3") (pin "P$1") (pinfunction "1_P$1") (pintype "bidirectional"))
    )
    (net (code "50") (name "Net-(IC6-CONF_DAT)") (class "Default")
      (node (ref "IC6") (pin "6") (pinfunction "CONF_DAT_6") (pintype "bidirectional"))
      (node (ref "TP101") (pin "P$1") (pinfunction "1_P$1") (pintype "bidirectional"))
      (node (ref "TP2") (pin "P$1") (pinfunction "1_P$1") (pintype "bidirectional"))
    )
    (net (code "51") (name "Net-(IC6-CS02)") (class "Default")
      (node (ref "IC6") (pin "20") (pinfunction "CS02_20") (pintype "bidirectional"))
      (node (ref "TB102") (pin "L") (pinfunction "LEFT_L") (pintype "bidirectional"))
    )
    (net (code "52") (name "Net-(IC6-CS03)") (class "Default")
      (node (ref "IC6") (pin "19") (pinfunction "CS03_19") (pintype "bidirectional"))
      (node (ref "TB102") (pin "UP") (pinfunction "UP_UP") (pintype "bidirectional"))
    )
    (net (code "53") (name "Net-(IC6-CS04)") (class "Default")
      (node (ref "IC6") (pin "18") (pinfunction "CS04_18") (pintype "bidirectional"))
      (node (ref "TB102") (pin "R") (pinfunction "RIGHT_R") (pintype "bidirectional"))
    )
    (net (code "54") (name "Net-(IC6-CS05)") (class "Default")
      (node (ref "IC6") (pin "17") (pinfunction "CS05_17") (pintype "bidirectional"))
      (node (ref "TB102") (pin "D") (pinfunction "DOWN_D") (pintype "bidirectional"))
    )
    (net (code "55") (name "Net-(IC6-CS07)") (class "Default")
      (node (ref "IC6") (pin "15") (pinfunction "CS07_15") (pintype "bidirectional"))
      (node (ref "TB100") (pin "P$1") (pinfunction "P$1_P$1") (pintype "bidirectional"))
    )
    (net (code "56") (name "Net-(IC6-CS08)") (class "Default")
      (node (ref "IC6") (pin "14") (pinfunction "CS08_14") (pintype "bidirectional"))
      (node (ref "TB101") (pin "P$1") (pinfunction "P$1_P$1") (pintype "bidirectional"))
    )
    (net (code "57") (name "Net-(IC6-CS09)") (class "Default")
      (node (ref "IC6") (pin "13") (pinfunction "CS09_13") (pintype "bidirectional"))
      (node (ref "TB103") (pin "P$1") (pinfunction "P$1_P$1") (pintype "bidirectional"))
    )
    (net (code "58") (name "Net-(IC6-CS11{slash}BUZZ)") (class "Default")
      (node (ref "IC6") (pin "10") (pinfunction "CS11/BUZZ_10") (pintype "bidirectional"))
      (node (ref "TB104") (pin "P$1") (pinfunction "P$1_P$1") (pintype "bidirectional"))
    )
    (net (code "59") (name "Net-(Q1-B)") (class "Default")
      (node (ref "Q1") (pin "1") (pinfunction "B_1") (pintype "passive"))
      (node (ref "R10") (pin "2") (pinfunction "2_2") (pintype "passive"))
    )
    (net (code "60") (name "Net-(Q1-C)") (class "Default")
      (node (ref "Q1") (pin "3") (pinfunction "C_3") (pintype "passive"))
      (node (ref "R9") (pin "1") (pinfunction "1_1") (pintype "passive"))
      (node (ref "T2") (pin "1") (pinfunction "G_1") (pintype "passive"))
    )
    (net (code "61") (name "Net-(Q2-B)") (class "Default")
      (node (ref "Q2") (pin "1") (pinfunction "B_1") (pintype "passive"))
      (node (ref "R11") (pin "1") (pinfunction "1_1") (pintype "passive"))
    )
    (net (code "62") (name "Net-(Q2-C)") (class "Default")
      (node (ref "Q2") (pin "3") (pinfunction "C_3") (pintype "passive"))
      (node (ref "U$1") (pin "-") (pinfunction "-_-") (pintype "bidirectional"))
    )
    (net (code "63") (name "Net-(Q3-B)") (class "Default")
      (node (ref "Q3") (pin "1") (pinfunction "B_1") (pintype "passive"))
      (node (ref "R18") (pin "2") (pinfunction "2_2") (pintype "passive"))
    )
    (net (code "64") (name "Net-(Q4-B)") (class "Default")
      (node (ref "Q4") (pin "1") (pinfunction "B_1") (pintype "passive"))
      (node (ref "R15") (pin "2") (pinfunction "2_2") (pintype "passive"))
    )
    (net (code "65") (name "Net-(Q5-D)") (class "Default")
      (node (ref "C25") (pin "2") (pinfunction "2_2") (pintype "passive"))
      (node (ref "D9") (pin "A") (pinfunction "A_A") (pintype "passive"))
      (node (ref "L1") (pin "2") (pinfunction "2_2") (pintype "passive"))
      (node (ref "Q5") (pin "3") (pinfunction "D_3") (pintype "passive"))
    )
    (net (code "66") (name "Net-(Q6-B)") (class "Default")
      (node (ref "Q6") (pin "1") (pinfunction "B_1") (pintype "passive"))
      (node (ref "R27") (pin "2") (pinfunction "2_2") (pintype "passive"))
    )
    (net (code "67") (name "Net-(Q6-C)") (class "Default")
      (node (ref "Q6") (pin "3") (pinfunction "C_3") (pintype "passive"))
      (node (ref "R28") (pin "1") (pinfunction "1_1") (pintype "passive"))
      (node (ref "T3") (pin "1") (pinfunction "G_1") (pintype "passive"))
    )
    (net (code "68") (name "Net-(R2-Pad1)") (class "Default")
      (node (ref "R2") (pin "1") (pinfunction "1_1") (pintype "passive"))
      (node (ref "U$1") (pin "+") (pinfunction "+_+") (pintype "bidirectional"))
    )
    (net (code "69") (name "Net-(R30-Pad1)") (class "Default")
      (node (ref "R30") (pin "1") (pinfunction "1_1") (pintype "passive"))
      (node (ref "R32") (pin "2") (pinfunction "2_2") (pintype "passive"))
      (node (ref "X4") (pin "1") (pinfunction "1_1") (pintype "passive"))
    )
    (net (code "70") (name "Net-(TP139-1)") (class "Default")
      (node (ref "F1") (pin "1") (pinfunction "1_1") (pintype "bidirectional"))
      (node (ref "TP139") (pin "P$1") (pinfunction "1_P$1") (pintype "bidirectional"))
      (node (ref "USB1") (pin "1") (pinfunction "1_1") (pintype "input"))
    )
    (net (code "71") (name "Net-(X2-NC)") (class "Default")
      (node (ref "R26") (pin "1") (pinfunction "1_1") (pintype "passive"))
      (node (ref "SJ1") (pin "2") (pinfunction "2_2") (pintype "passive"))
      (node (ref "X2") (pin "1") (pinfunction "NC_1") (pintype "bidirectional"))
    )
    (net (code "72") (name "Net-(X2-RSV)") (class "Default")
      (node (ref "SJ2") (pin "2") (pinfunction "2_2") (pintype "passive"))
      (node (ref "X2") (pin "8") (pinfunction "RSV_8") (pintype "bidirectional"))
    )
    (net (code "73") (name "Net-(X4C-1)") (class "Default")
      (node (ref "C34") (pin "1") (pinfunction "1_1") (pintype "passive"))
      (node (ref "F2") (pin "1") (pinfunction "1_1") (pintype "bidirectional"))
      (node (ref "IC4") (pin "10") (pinfunction "VBAT_10") (pintype "bidirectional"))
      (node (ref "IC4") (pin "9") (pinfunction "VBAT_9") (pintype "bidirectional"))
      (node (ref "X4") (pin "3") (pinfunction "1_3") (pintype "passive"))
    )
    (net (code "74") (name "PREVGH") (class "Default")
      (node (ref "C32") (pin "2") (pinfunction "2_2") (pintype "passive"))
      (node (ref "D9") (pin "C") (pinfunction "C_C") (pintype "passive"))
      (node (ref "TP104") (pin "P$1") (pinfunction "1_P$1") (pintype "bidirectional"))
      (node (ref "X1") (pin "4") (pinfunction "4_4") (pintype "passive"))
    )
    (net (code "75") (name "PREVGL") (class "Default")
      (node (ref "C36") (pin "2") (pinfunction "2_2") (pintype "passive"))
      (node (ref "D8") (pin "A") (pinfunction "A_A") (pintype "passive"))
      (node (ref "TP105") (pin "P$1") (pinfunction "1_P$1") (pintype "bidirectional"))
      (node (ref "X1") (pin "2") (pinfunction "2_2") (pintype "passive"))
    )
    (net (code "76") (name "PROXIMITY") (class "Default")
      (node (ref "IC6") (pin "2") (pinfunction "CS00_2") (pintype "bidirectional"))
    )
    (net (code "77") (name "RESE") (class "Default")
      (node (ref "Q5") (pin "2") (pinfunction "S_2") (pintype "passive"))
      (node (ref "R19") (pin "1") (pinfunction "1_1") (pintype "passive"))
      (node (ref "TP123") (pin "P$1") (pinfunction "1_P$1") (pintype "bidirectional"))
      (node (ref "X1") (pin "22") (pinfunction "22_22") (pintype "passive"))
    )
    (net (code "78") (name "SD_CD") (class "Default")
      (node (ref "IC5") (pin "6") (pinfunction "GPIO4_6") (pintype "bidirectional"))
      (node (ref "R31") (pin "2") (pinfunction "2_2") (pintype "passive"))
      (node (ref "X2") (pin "CD1") (pinfunction "SHIELD_CD1") (pintype "bidirectional"))
    )
    (net (code "79") (name "SD_CLK") (class "Default")
      (node (ref "IC3") (pin "13") (pinfunction "IO14_13") (pintype "bidirectional"))
      (node (ref "R25") (pin "1") (pinfunction "1_1") (pintype "passive"))
      (node (ref "X2") (pin "5") (pinfunction "SCK_5") (pintype "bidirectional"))
    )
    (net (code "80") (name "SD_CMD") (class "Default")
      (node (ref "IC3") (pin "23") (pinfunction "IO15_23") (pintype "bidirectional"))
      (node (ref "R8") (pin "1") (pinfunction "1_1") (pintype "passive"))
      (node (ref "X2") (pin "3") (pinfunction "DI_3") (pintype "bidirectional"))
    )
    (net (code "81") (name "SD_DATA0") (class "Default")
      (node (ref "D2") (pin "A") (pinfunction "A_A") (pintype "passive"))
      (node (ref "IC3") (pin "24") (pinfunction "IO2_24") (pintype "bidirectional"))
      (node (ref "R5") (pin "1") (pinfunction "1_1") (pintype "passive"))
      (node (ref "X2") (pin "7") (pinfunction "DO_7") (pintype "bidirectional"))
    )
    (net (code "82") (name "SD_DATA1") (class "Default")
      (node (ref "IC3") (pin "26") (pinfunction "IO4_26") (pintype "bidirectional"))
      (node (ref "R1") (pin "1") (pinfunction "1_1") (pintype "passive"))
      (node (ref "SJ2") (pin "1") (pinfunction "1_1") (pintype "passive"))
    )
    (net (code "83") (name "SD_DATA2") (class "Default")
      (node (ref "IC3") (pin "14") (pinfunction "IO12_14") (pintype "bidirectional"))
      (node (ref "SJ1") (pin "1") (pinfunction "1_1") (pintype "passive"))
    )
    (net (code "84") (name "SD_DATA3") (class "Default")
      (node (ref "IC3") (pin "16") (pinfunction "IO13_16") (pintype "bidirectional"))
      (node (ref "R17") (pin "1") (pinfunction "1_1") (pintype "passive"))
      (node (ref "X2") (pin "2") (pinfunction "CS_2") (pintype "bidirectional"))
    )
    (net (code "85") (name "TOUCH_INT") (class "Default")
      (node (ref "IC5") (pin "7") (pinfunction "GPIO3_7") (pintype "bidirectional"))
      (node (ref "IC6") (pin "7") (pinfunction "EB_INT_7") (pintype "bidirectional"))
    )
    (net (code "86") (name "TSCL") (class "Default")
      (node (ref "X1") (pin "19") (pinfunction "19_19") (pintype "passive"))
    )
    (net (code "87") (name "TSDA") (class "Default")
      (node (ref "X1") (pin "18") (pinfunction "18_18") (pintype "passive"))
    )
    (net (code "88") (name "USB_DN_CON") (class "Default")
      (node (ref "IC1") (pin "5") (pinfunction "D-_5") (pintype "bidirectional"))
      (node (ref "TP137") (pin "P$1") (pinfunction "1_P$1") (pintype "bidirectional"))
      (node (ref "USB1") (pin "2") (pinfunction "2_2") (pintype "input"))
    )
    (net (code "89") (name "USB_DP_CON") (class "Default")
      (node (ref "IC1") (pin "4") (pinfunction "D+_4") (pintype "bidirectional"))
      (node (ref "TP138") (pin "P$1") (pinfunction "1_P$1") (pintype "bidirectional"))
      (node (ref "USB1") (pin "3") (pinfunction "3_3") (pintype "input"))
    )
    (net (code "90") (name "VBAT") (class "Default")
      (node (ref "F2") (pin "2") (pinfunction "2_2") (pintype "bidirectional"))
      (node (ref "R21") (pin "2") (pinfunction "2_2") (pintype "passive"))
      (node (ref "T1") (pin "3") (pinfunction "D_3") (pintype "passive"))
      (node (ref "TP110") (pin "P$1") (pinfunction "1_P$1") (pintype "bidirectional"))
    )
    (net (code "91") (name "VBAT_SENSE") (class "Default")
      (node (ref "C16") (pin "1") (pinfunction "1_1") (pintype "passive"))
      (node (ref "IC3") (pin "7") (pinfunction "IO35_7") (pintype "bidirectional"))
      (node (ref "R20") (pin "2") (pinfunction "2_2") (pintype "passive"))
      (node (ref "R21") (pin "1") (pinfunction "1_1") (pintype "passive"))
    )
    (net (code "92") (name "VCC") (class "Default")
      (node (ref "C14") (pin "1") (pinfunction "1_1") (pintype "passive"))
      (node (ref "C15") (pin "1") (pinfunction "1_1") (pintype "passive"))
      (node (ref "C18") (pin "1") (pinfunction "1_1") (pintype "passive"))
      (node (ref "D3") (pin "C") (pinfunction "C_C") (pintype "passive"))
      (node (ref "IC2") (pin "2") (pinfunction "IN_2") (pintype "input"))
      (node (ref "IC2") (pin "2@") (pinfunction "IN_2@") (pintype "input"))
      (node (ref "R2") (pin "2") (pinfunction "2_2") (pintype "passive"))
      (node (ref "R9") (pin "2") (pinfunction "2_2") (pintype "passive"))
      (node (ref "T1") (pin "2") (pinfunction "S_2") (pintype "passive"))
      (node (ref "T2") (pin "2") (pinfunction "S_2") (pintype "passive"))
      (node (ref "TP129") (pin "P$1") (pinfunction "1_P$1") (pintype "bidirectional"))
    )
    (net (code "93") (name "VCOM") (class "Default")
      (node (ref "C38") (pin "2") (pinfunction "2_2") (pintype "passive"))
      (node (ref "X1") (pin "1") (pinfunction "1_1") (pintype "passive"))
    )
    (net (code "94") (name "VDD") (class "Default")
      (node (ref "C8") (pin "1") (pinfunction "1_1") (pintype "passive"))
      (node (ref "IC1") (pin "6") (pinfunction "VDD_6") (pintype "power_in"))
      (node (ref "R12") (pin "2") (pinfunction "2_2") (pintype "passive"))
      (node (ref "R13") (pin "1") (pinfunction "1_1") (pintype "passive"))
      (node (ref "R14") (pin "2") (pinfunction "2_2") (pintype "passive"))
      (node (ref "R3") (pin "2") (pinfunction "2_2") (pintype "passive"))
    )
    (net (code "95") (name "VGH") (class "Default")
      (node (ref "C21") (pin "2") (pinfunction "2_2") (pintype "passive"))
      (node (ref "X1") (pin "20") (pinfunction "20_20") (pintype "passive"))
    )
    (net (code "96") (name "VGL") (class "Default")
      (node (ref "C19") (pin "2") (pinfunction "2_2") (pintype "passive"))
      (node (ref "X1") (pin "21") (pinfunction "21_21") (pintype "passive"))
    )
    (net (code "97") (name "VIBRATOR") (class "Default")
      (node (ref "IC5") (pin "11") (pinfunction "GPIO1_11") (pintype "bidirectional"))
      (node (ref "R11") (pin "2") (pinfunction "2_2") (pintype "passive"))
    )
    (net (code "98") (name "VPP") (class "Default")
      (node (ref "X1") (pin "6") (pinfunction "6_6") (pintype "passive"))
    )
    (net (code "99") (name "VSH") (class "Default")
      (node (ref "C33") (pin "2") (pinfunction "2_2") (pintype "passive"))
      (node (ref "X1") (pin "5") (pinfunction "5_5") (pintype "passive"))
    )
    (net (code "100") (name "VSL") (class "Default")
      (node (ref "C35") (pin "2") (pinfunction "2_2") (pintype "passive"))
      (node (ref "X1") (pin "3") (pinfunction "3_3") (pintype "passive"))
    )
    (net (code "101") (name "VUSB_SENSE") (class "Default")
      (node (ref "C10") (pin "1") (pinfunction "1_1") (pintype "passive"))
      (node (ref "IC3") (pin "6") (pinfunction "IO34_6") (pintype "bidirectional"))
      (node (ref "R6") (pin "2") (pinfunction "2_2") (pintype "passive"))
      (node (ref "R7") (pin "1") (pinfunction "1_1") (pintype "passive"))
    )
    (net (code "102") (name "WS2812_DATA") (class "Default")
      (node (ref "D105") (pin "4") (pinfunction "DIN_4") (pintype "input"))
      (node (ref "IC3") (pin "8") (pinfunction "IO32_8") (pintype "bidirectional"))
      (node (ref "TP136") (pin "P$1") (pinfunction "1_P$1") (pintype "bidirectional"))
    )
    (net (code "103") (name "WS2812_DATA_OUT") (class "Default")
      (node (ref "D100") (pin "2") (pinfunction "DOUT_2") (pintype "output"))
      (node (ref "X3") (pin "8") (pinfunction "5_8") (pintype "passive"))
    )
    (net (code "104") (name "WS2812_POWER") (class "Default")
      (node (ref "C1") (pin "2") (pinfunction "2_2") (pintype "passive"))
      (node (ref "C13") (pin "1") (pinfunction "1_1") (pintype "passive"))
      (node (ref "C2") (pin "2") (pinfunction "2_2") (pintype "passive"))
      (node (ref "C3") (pin "2") (pinfunction "2_2") (pintype "passive"))
      (node (ref "C4") (pin "2") (pinfunction "2_2") (pintype "passive"))
      (node (ref "C5") (pin "2") (pinfunction "2_2") (pintype "passive"))
      (node (ref "C6") (pin "2") (pinfunction "2_2") (pintype "passive"))
      (node (ref "D100") (pin "1") (pinfunction "VDD_1") (pintype "power_in"))
      (node (ref "D101") (pin "1") (pinfunction "VDD_1") (pintype "power_in"))
      (node (ref "D102") (pin "1") (pinfunction "VDD_1") (pintype "power_in"))
      (node (ref "D103") (pin "1") (pinfunction "VDD_1") (pintype "power_in"))
      (node (ref "D104") (pin "1") (pinfunction "VDD_1") (pintype "power_in"))
      (node (ref "D105") (pin "1") (pinfunction "VDD_1") (pintype "power_in"))
      (node (ref "T2") (pin "3") (pinfunction "D_3") (pintype "passive"))
      (node (ref "TP117") (pin "P$1") (pinfunction "1_P$1") (pintype "bidirectional"))
      (node (ref "X3") (pin "2") (pinfunction "11_2") (pintype "passive"))
    )
    (net (code "105") (name "WS2812_POWER_EN") (class "Default")
      (node (ref "IC5") (pin "8") (pinfunction "GPIO2_8") (pintype "bidirectional"))
      (node (ref "R10") (pin "1") (pinfunction "1_1") (pintype "passive"))
      (node (ref "R27") (pin "1") (pinfunction "1_1") (pintype "passive"))
    )
    (net (code "106") (name "unconnected-(IC1-CTS-Pad23)") (class "Default")
      (node (ref "IC1") (pin "23") (pinfunction "CTS_23") (pintype "input"))
    )
    (net (code "107") (name "unconnected-(IC1-DCD-Pad1)") (class "Default")
      (node (ref "IC1") (pin "1") (pinfunction "DCD_1") (pintype "input"))
    )
    (net (code "108") (name "unconnected-(IC1-DSR-Pad27)") (class "Default")
      (node (ref "IC1") (pin "27") (pinfunction "DSR_27") (pintype "input"))
    )
    (net (code "109") (name "unconnected-(IC1-RI-Pad2)") (class "Default")
      (node (ref "IC1") (pin "2") (pinfunction "RI_2") (pintype "input"))
    )
    (net (code "110") (name "unconnected-(IC1-SUSPEND-Pad12)") (class "Default")
      (node (ref "IC1") (pin "12") (pinfunction "SUSPEND_12") (pintype "output"))
    )
    (net (code "111") (name "unconnected-(IC1-~{SUSPEND}-Pad11)") (class "Default")
      (node (ref "IC1") (pin "11") (pinfunction "~{SUSPEND}_11") (pintype "output"))
    )
    (net (code "112") (name "unconnected-(IC3-IO20-Pad32)") (class "Default")
      (node (ref "IC3") (pin "32") (pinfunction "IO20_32") (pintype "bidirectional"))
    )
    (net (code "113") (name "unconnected-(IC4-STAT2-Pad4)") (class "Default")
      (node (ref "IC4") (pin "4") (pinfunction "STAT2_4") (pintype "bidirectional"))
    )
    (net (code "114") (name "unconnected-(IC4-~{PG}-Pad7)") (class "Default")
      (node (ref "IC4") (pin "7") (pinfunction "~{PG}_7") (pintype "bidirectional"))
    )
    (net (code "115") (name "unconnected-(IC6-CS01-Pad1)") (class "Default")
      (node (ref "IC6") (pin "1") (pinfunction "CS01_1") (pintype "bidirectional"))
    )
    (net (code "116") (name "unconnected-(IC6-CS06-Pad16)") (class "Default")
      (node (ref "IC6") (pin "16") (pinfunction "CS06_16") (pintype "bidirectional"))
    )
    (net (code "117") (name "unconnected-(IC6-CS10-Pad11)") (class "Default")
      (node (ref "IC6") (pin "11") (pinfunction "CS10_11") (pintype "bidirectional"))
    )
    (net (code "118") (name "unconnected-(USB1-Pad4)") (class "Default")
      (node (ref "USB1") (pin "4") (pinfunction "4_4") (pintype "input"))
    )
    (net (code "119") (name "unconnected-(X1-Pad24)") (class "Default")
      (node (ref "X1") (pin "24") (pinfunction "24_24") (pintype "passive"))
    )
  )
)
